# coil.net
KiCad netlist of a schematic drawn in EAGLE
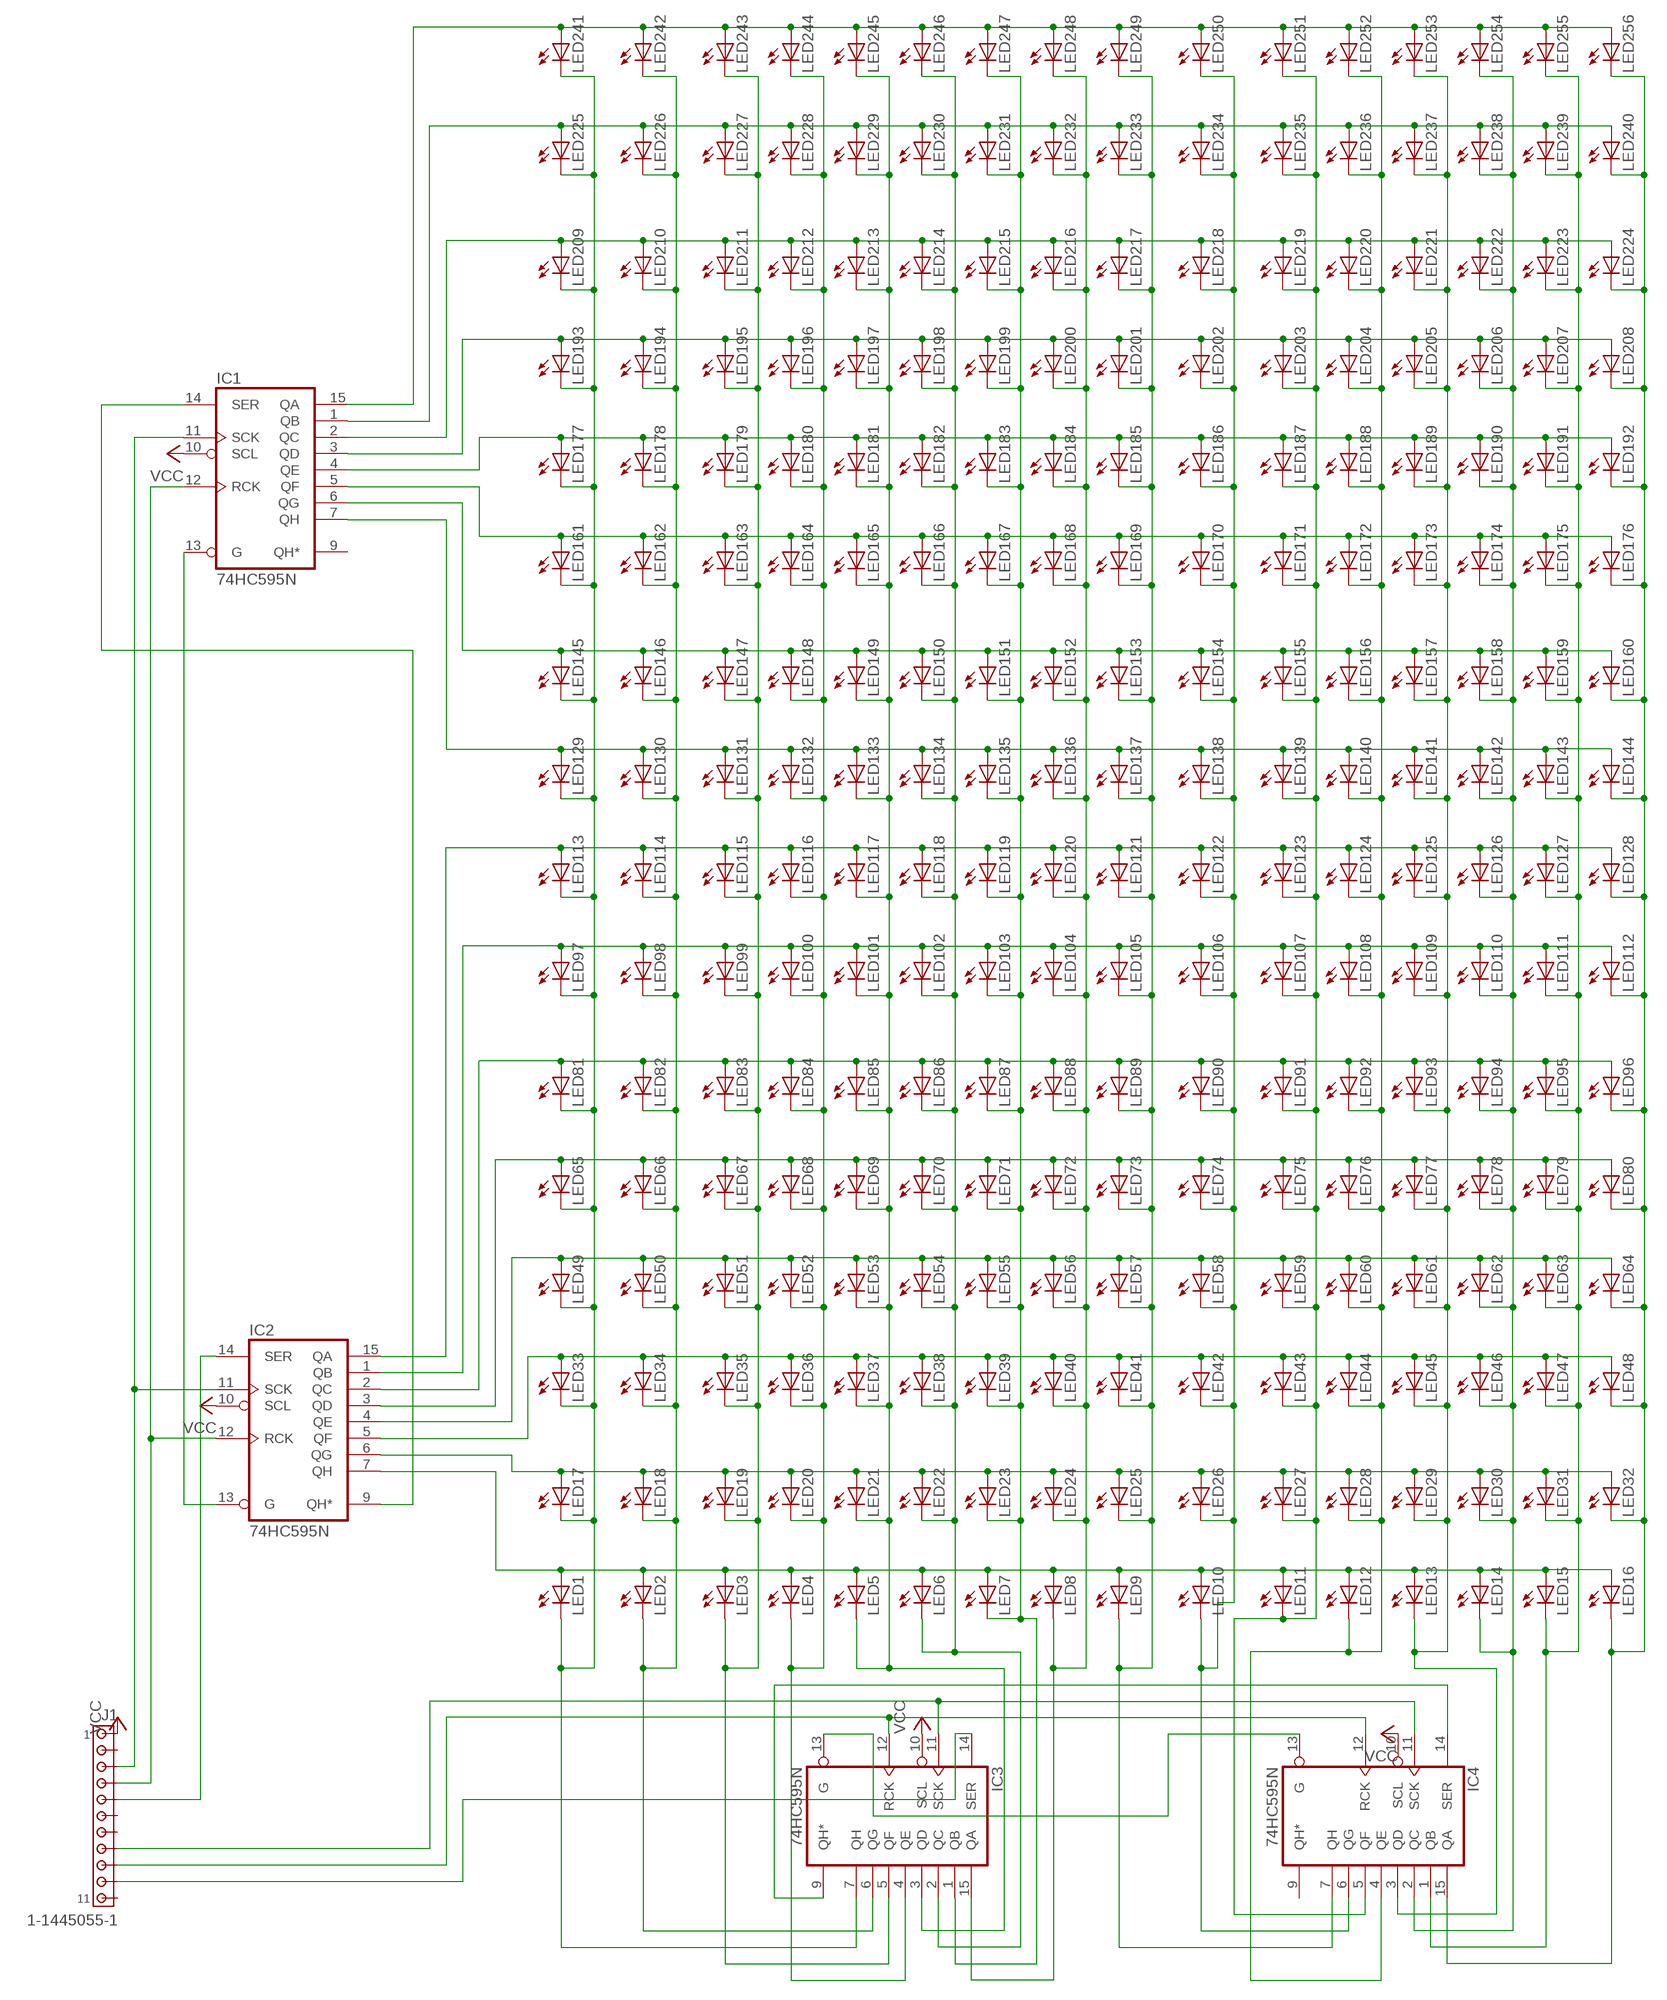
[diagram p0: schematic, sheet 1]

(export (version "E")
  (design (tool "Eeschema 10.0.6"))
  (components
    (comp (ref "IC1")
      (value "74HC595N")
      (footprint "eagle-import:DIL16")
      (libsource (lib "eagle-import") (part "74595NHC"))
    )
    (comp (ref "IC2")
      (value "74HC595N")
      (footprint "eagle-import:DIL16")
      (libsource (lib "eagle-import") (part "74595NHC"))
    )
    (comp (ref "IC3")
      (value "74HC595N")
      (footprint "eagle-import:DIL16")
      (libsource (lib "eagle-import") (part "74595NHC"))
    )
    (comp (ref "IC4")
      (value "74HC595N")
      (footprint "eagle-import:DIL16")
      (libsource (lib "eagle-import") (part "74595NHC"))
    )
    (comp (ref "J1")
      (value "1-1445055-1")
      (footprint "eagle-import:1-1445055-1")
      (libsource (lib "eagle-import") (part "1-1445055-1"))
    )
    (comp (ref "LED1")
      (value "LED5MM")
      (footprint "eagle-import:LED5MM")
      (libsource (lib "eagle-import") (part "LED5MM"))
    )
    (comp (ref "LED2")
      (value "LED5MM")
      (footprint "eagle-import:LED5MM")
      (libsource (lib "eagle-import") (part "LED5MM"))
    )
    (comp (ref "LED3")
      (value "LED5MM")
      (footprint "eagle-import:LED5MM")
      (libsource (lib "eagle-import") (part "LED5MM"))
    )
    (comp (ref "LED4")
      (value "LED5MM")
      (footprint "eagle-import:LED5MM")
      (libsource (lib "eagle-import") (part "LED5MM"))
    )
    (comp (ref "LED5")
      (value "LED5MM")
      (footprint "eagle-import:LED5MM")
      (libsource (lib "eagle-import") (part "LED5MM"))
    )
    (comp (ref "LED6")
      (value "LED5MM")
      (footprint "eagle-import:LED5MM")
      (libsource (lib "eagle-import") (part "LED5MM"))
    )
    (comp (ref "LED7")
      (value "LED5MM")
      (footprint "eagle-import:LED5MM")
      (libsource (lib "eagle-import") (part "LED5MM"))
    )
    (comp (ref "LED8")
      (value "LED5MM")
      (footprint "eagle-import:LED5MM")
      (libsource (lib "eagle-import") (part "LED5MM"))
    )
    (comp (ref "LED9")
      (value "LED5MM")
      (footprint "eagle-import:LED5MM")
      (libsource (lib "eagle-import") (part "LED5MM"))
    )
    (comp (ref "LED10")
      (value "LED5MM")
      (footprint "eagle-import:LED5MM")
      (libsource (lib "eagle-import") (part "LED5MM"))
    )
    (comp (ref "LED11")
      (value "LED5MM")
      (footprint "eagle-import:LED5MM")
      (libsource (lib "eagle-import") (part "LED5MM"))
    )
    (comp (ref "LED12")
      (value "LED5MM")
      (footprint "eagle-import:LED5MM")
      (libsource (lib "eagle-import") (part "LED5MM"))
    )
    (comp (ref "LED13")
      (value "LED5MM")
      (footprint "eagle-import:LED5MM")
      (libsource (lib "eagle-import") (part "LED5MM"))
    )
    (comp (ref "LED14")
      (value "LED5MM")
      (footprint "eagle-import:LED5MM")
      (libsource (lib "eagle-import") (part "LED5MM"))
    )
    (comp (ref "LED15")
      (value "LED5MM")
      (footprint "eagle-import:LED5MM")
      (libsource (lib "eagle-import") (part "LED5MM"))
    )
    (comp (ref "LED16")
      (value "LED5MM")
      (footprint "eagle-import:LED5MM")
      (libsource (lib "eagle-import") (part "LED5MM"))
    )
    (comp (ref "LED17")
      (value "LED5MM")
      (footprint "eagle-import:LED5MM")
      (libsource (lib "eagle-import") (part "LED5MM"))
    )
    (comp (ref "LED18")
      (value "LED5MM")
      (footprint "eagle-import:LED5MM")
      (libsource (lib "eagle-import") (part "LED5MM"))
    )
    (comp (ref "LED19")
      (value "LED5MM")
      (footprint "eagle-import:LED5MM")
      (libsource (lib "eagle-import") (part "LED5MM"))
    )
    (comp (ref "LED20")
      (value "LED5MM")
      (footprint "eagle-import:LED5MM")
      (libsource (lib "eagle-import") (part "LED5MM"))
    )
    (comp (ref "LED21")
      (value "LED5MM")
      (footprint "eagle-import:LED5MM")
      (libsource (lib "eagle-import") (part "LED5MM"))
    )
    (comp (ref "LED22")
      (value "LED5MM")
      (footprint "eagle-import:LED5MM")
      (libsource (lib "eagle-import") (part "LED5MM"))
    )
    (comp (ref "LED23")
      (value "LED5MM")
      (footprint "eagle-import:LED5MM")
      (libsource (lib "eagle-import") (part "LED5MM"))
    )
    (comp (ref "LED24")
      (value "LED5MM")
      (footprint "eagle-import:LED5MM")
      (libsource (lib "eagle-import") (part "LED5MM"))
    )
    (comp (ref "LED25")
      (value "LED5MM")
      (footprint "eagle-import:LED5MM")
      (libsource (lib "eagle-import") (part "LED5MM"))
    )
    (comp (ref "LED26")
      (value "LED5MM")
      (footprint "eagle-import:LED5MM")
      (libsource (lib "eagle-import") (part "LED5MM"))
    )
    (comp (ref "LED27")
      (value "LED5MM")
      (footprint "eagle-import:LED5MM")
      (libsource (lib "eagle-import") (part "LED5MM"))
    )
    (comp (ref "LED28")
      (value "LED5MM")
      (footprint "eagle-import:LED5MM")
      (libsource (lib "eagle-import") (part "LED5MM"))
    )
    (comp (ref "LED29")
      (value "LED5MM")
      (footprint "eagle-import:LED5MM")
      (libsource (lib "eagle-import") (part "LED5MM"))
    )
    (comp (ref "LED30")
      (value "LED5MM")
      (footprint "eagle-import:LED5MM")
      (libsource (lib "eagle-import") (part "LED5MM"))
    )
    (comp (ref "LED31")
      (value "LED5MM")
      (footprint "eagle-import:LED5MM")
      (libsource (lib "eagle-import") (part "LED5MM"))
    )
    (comp (ref "LED32")
      (value "LED5MM")
      (footprint "eagle-import:LED5MM")
      (libsource (lib "eagle-import") (part "LED5MM"))
    )
    (comp (ref "LED33")
      (value "LED5MM")
      (footprint "eagle-import:LED5MM")
      (libsource (lib "eagle-import") (part "LED5MM"))
    )
    (comp (ref "LED34")
      (value "LED5MM")
      (footprint "eagle-import:LED5MM")
      (libsource (lib "eagle-import") (part "LED5MM"))
    )
    (comp (ref "LED35")
      (value "LED5MM")
      (footprint "eagle-import:LED5MM")
      (libsource (lib "eagle-import") (part "LED5MM"))
    )
    (comp (ref "LED36")
      (value "LED5MM")
      (footprint "eagle-import:LED5MM")
      (libsource (lib "eagle-import") (part "LED5MM"))
    )
    (comp (ref "LED37")
      (value "LED5MM")
      (footprint "eagle-import:LED5MM")
      (libsource (lib "eagle-import") (part "LED5MM"))
    )
    (comp (ref "LED38")
      (value "LED5MM")
      (footprint "eagle-import:LED5MM")
      (libsource (lib "eagle-import") (part "LED5MM"))
    )
    (comp (ref "LED39")
      (value "LED5MM")
      (footprint "eagle-import:LED5MM")
      (libsource (lib "eagle-import") (part "LED5MM"))
    )
    (comp (ref "LED40")
      (value "LED5MM")
      (footprint "eagle-import:LED5MM")
      (libsource (lib "eagle-import") (part "LED5MM"))
    )
    (comp (ref "LED41")
      (value "LED5MM")
      (footprint "eagle-import:LED5MM")
      (libsource (lib "eagle-import") (part "LED5MM"))
    )
    (comp (ref "LED42")
      (value "LED5MM")
      (footprint "eagle-import:LED5MM")
      (libsource (lib "eagle-import") (part "LED5MM"))
    )
    (comp (ref "LED43")
      (value "LED5MM")
      (footprint "eagle-import:LED5MM")
      (libsource (lib "eagle-import") (part "LED5MM"))
    )
    (comp (ref "LED44")
      (value "LED5MM")
      (footprint "eagle-import:LED5MM")
      (libsource (lib "eagle-import") (part "LED5MM"))
    )
    (comp (ref "LED45")
      (value "LED5MM")
      (footprint "eagle-import:LED5MM")
      (libsource (lib "eagle-import") (part "LED5MM"))
    )
    (comp (ref "LED46")
      (value "LED5MM")
      (footprint "eagle-import:LED5MM")
      (libsource (lib "eagle-import") (part "LED5MM"))
    )
    (comp (ref "LED47")
      (value "LED5MM")
      (footprint "eagle-import:LED5MM")
      (libsource (lib "eagle-import") (part "LED5MM"))
    )
    (comp (ref "LED48")
      (value "LED5MM")
      (footprint "eagle-import:LED5MM")
      (libsource (lib "eagle-import") (part "LED5MM"))
    )
    (comp (ref "LED49")
      (value "LED5MM")
      (footprint "eagle-import:LED5MM")
      (libsource (lib "eagle-import") (part "LED5MM"))
    )
    (comp (ref "LED50")
      (value "LED5MM")
      (footprint "eagle-import:LED5MM")
      (libsource (lib "eagle-import") (part "LED5MM"))
    )
    (comp (ref "LED51")
      (value "LED5MM")
      (footprint "eagle-import:LED5MM")
      (libsource (lib "eagle-import") (part "LED5MM"))
    )
    (comp (ref "LED52")
      (value "LED5MM")
      (footprint "eagle-import:LED5MM")
      (libsource (lib "eagle-import") (part "LED5MM"))
    )
    (comp (ref "LED53")
      (value "LED5MM")
      (footprint "eagle-import:LED5MM")
      (libsource (lib "eagle-import") (part "LED5MM"))
    )
    (comp (ref "LED54")
      (value "LED5MM")
      (footprint "eagle-import:LED5MM")
      (libsource (lib "eagle-import") (part "LED5MM"))
    )
    (comp (ref "LED55")
      (value "LED5MM")
      (footprint "eagle-import:LED5MM")
      (libsource (lib "eagle-import") (part "LED5MM"))
    )
    (comp (ref "LED56")
      (value "LED5MM")
      (footprint "eagle-import:LED5MM")
      (libsource (lib "eagle-import") (part "LED5MM"))
    )
    (comp (ref "LED57")
      (value "LED5MM")
      (footprint "eagle-import:LED5MM")
      (libsource (lib "eagle-import") (part "LED5MM"))
    )
    (comp (ref "LED58")
      (value "LED5MM")
      (footprint "eagle-import:LED5MM")
      (libsource (lib "eagle-import") (part "LED5MM"))
    )
    (comp (ref "LED59")
      (value "LED5MM")
      (footprint "eagle-import:LED5MM")
      (libsource (lib "eagle-import") (part "LED5MM"))
    )
    (comp (ref "LED60")
      (value "LED5MM")
      (footprint "eagle-import:LED5MM")
      (libsource (lib "eagle-import") (part "LED5MM"))
    )
    (comp (ref "LED61")
      (value "LED5MM")
      (footprint "eagle-import:LED5MM")
      (libsource (lib "eagle-import") (part "LED5MM"))
    )
    (comp (ref "LED62")
      (value "LED5MM")
      (footprint "eagle-import:LED5MM")
      (libsource (lib "eagle-import") (part "LED5MM"))
    )
    (comp (ref "LED63")
      (value "LED5MM")
      (footprint "eagle-import:LED5MM")
      (libsource (lib "eagle-import") (part "LED5MM"))
    )
    (comp (ref "LED64")
      (value "LED5MM")
      (footprint "eagle-import:LED5MM")
      (libsource (lib "eagle-import") (part "LED5MM"))
    )
    (comp (ref "LED65")
      (value "LED5MM")
      (footprint "eagle-import:LED5MM")
      (libsource (lib "eagle-import") (part "LED5MM"))
    )
    (comp (ref "LED66")
      (value "LED5MM")
      (footprint "eagle-import:LED5MM")
      (libsource (lib "eagle-import") (part "LED5MM"))
    )
    (comp (ref "LED67")
      (value "LED5MM")
      (footprint "eagle-import:LED5MM")
      (libsource (lib "eagle-import") (part "LED5MM"))
    )
    (comp (ref "LED68")
      (value "LED5MM")
      (footprint "eagle-import:LED5MM")
      (libsource (lib "eagle-import") (part "LED5MM"))
    )
    (comp (ref "LED69")
      (value "LED5MM")
      (footprint "eagle-import:LED5MM")
      (libsource (lib "eagle-import") (part "LED5MM"))
    )
    (comp (ref "LED70")
      (value "LED5MM")
      (footprint "eagle-import:LED5MM")
      (libsource (lib "eagle-import") (part "LED5MM"))
    )
    (comp (ref "LED71")
      (value "LED5MM")
      (footprint "eagle-import:LED5MM")
      (libsource (lib "eagle-import") (part "LED5MM"))
    )
    (comp (ref "LED72")
      (value "LED5MM")
      (footprint "eagle-import:LED5MM")
      (libsource (lib "eagle-import") (part "LED5MM"))
    )
    (comp (ref "LED73")
      (value "LED5MM")
      (footprint "eagle-import:LED5MM")
      (libsource (lib "eagle-import") (part "LED5MM"))
    )
    (comp (ref "LED74")
      (value "LED5MM")
      (footprint "eagle-import:LED5MM")
      (libsource (lib "eagle-import") (part "LED5MM"))
    )
    (comp (ref "LED75")
      (value "LED5MM")
      (footprint "eagle-import:LED5MM")
      (libsource (lib "eagle-import") (part "LED5MM"))
    )
    (comp (ref "LED76")
      (value "LED5MM")
      (footprint "eagle-import:LED5MM")
      (libsource (lib "eagle-import") (part "LED5MM"))
    )
    (comp (ref "LED77")
      (value "LED5MM")
      (footprint "eagle-import:LED5MM")
      (libsource (lib "eagle-import") (part "LED5MM"))
    )
    (comp (ref "LED78")
      (value "LED5MM")
      (footprint "eagle-import:LED5MM")
      (libsource (lib "eagle-import") (part "LED5MM"))
    )
    (comp (ref "LED79")
      (value "LED5MM")
      (footprint "eagle-import:LED5MM")
      (libsource (lib "eagle-import") (part "LED5MM"))
    )
    (comp (ref "LED80")
      (value "LED5MM")
      (footprint "eagle-import:LED5MM")
      (libsource (lib "eagle-import") (part "LED5MM"))
    )
    (comp (ref "LED81")
      (value "LED5MM")
      (footprint "eagle-import:LED5MM")
      (libsource (lib "eagle-import") (part "LED5MM"))
    )
    (comp (ref "LED82")
      (value "LED5MM")
      (footprint "eagle-import:LED5MM")
      (libsource (lib "eagle-import") (part "LED5MM"))
    )
    (comp (ref "LED83")
      (value "LED5MM")
      (footprint "eagle-import:LED5MM")
      (libsource (lib "eagle-import") (part "LED5MM"))
    )
    (comp (ref "LED84")
      (value "LED5MM")
      (footprint "eagle-import:LED5MM")
      (libsource (lib "eagle-import") (part "LED5MM"))
    )
    (comp (ref "LED85")
      (value "LED5MM")
      (footprint "eagle-import:LED5MM")
      (libsource (lib "eagle-import") (part "LED5MM"))
    )
    (comp (ref "LED86")
      (value "LED5MM")
      (footprint "eagle-import:LED5MM")
      (libsource (lib "eagle-import") (part "LED5MM"))
    )
    (comp (ref "LED87")
      (value "LED5MM")
      (footprint "eagle-import:LED5MM")
      (libsource (lib "eagle-import") (part "LED5MM"))
    )
    (comp (ref "LED88")
      (value "LED5MM")
      (footprint "eagle-import:LED5MM")
      (libsource (lib "eagle-import") (part "LED5MM"))
    )
    (comp (ref "LED89")
      (value "LED5MM")
      (footprint "eagle-import:LED5MM")
      (libsource (lib "eagle-import") (part "LED5MM"))
    )
    (comp (ref "LED90")
      (value "LED5MM")
      (footprint "eagle-import:LED5MM")
      (libsource (lib "eagle-import") (part "LED5MM"))
    )
    (comp (ref "LED91")
      (value "LED5MM")
      (footprint "eagle-import:LED5MM")
      (libsource (lib "eagle-import") (part "LED5MM"))
    )
    (comp (ref "LED92")
      (value "LED5MM")
      (footprint "eagle-import:LED5MM")
      (libsource (lib "eagle-import") (part "LED5MM"))
    )
    (comp (ref "LED93")
      (value "LED5MM")
      (footprint "eagle-import:LED5MM")
      (libsource (lib "eagle-import") (part "LED5MM"))
    )
    (comp (ref "LED94")
      (value "LED5MM")
      (footprint "eagle-import:LED5MM")
      (libsource (lib "eagle-import") (part "LED5MM"))
    )
    (comp (ref "LED95")
      (value "LED5MM")
      (footprint "eagle-import:LED5MM")
      (libsource (lib "eagle-import") (part "LED5MM"))
    )
    (comp (ref "LED96")
      (value "LED5MM")
      (footprint "eagle-import:LED5MM")
      (libsource (lib "eagle-import") (part "LED5MM"))
    )
    (comp (ref "LED97")
      (value "LED5MM")
      (footprint "eagle-import:LED5MM")
      (libsource (lib "eagle-import") (part "LED5MM"))
    )
    (comp (ref "LED98")
      (value "LED5MM")
      (footprint "eagle-import:LED5MM")
      (libsource (lib "eagle-import") (part "LED5MM"))
    )
    (comp (ref "LED99")
      (value "LED5MM")
      (footprint "eagle-import:LED5MM")
      (libsource (lib "eagle-import") (part "LED5MM"))
    )
    (comp (ref "LED100")
      (value "LED5MM")
      (footprint "eagle-import:LED5MM")
      (libsource (lib "eagle-import") (part "LED5MM"))
    )
    (comp (ref "LED101")
      (value "LED5MM")
      (footprint "eagle-import:LED5MM")
      (libsource (lib "eagle-import") (part "LED5MM"))
    )
    (comp (ref "LED102")
      (value "LED5MM")
      (footprint "eagle-import:LED5MM")
      (libsource (lib "eagle-import") (part "LED5MM"))
    )
    (comp (ref "LED103")
      (value "LED5MM")
      (footprint "eagle-import:LED5MM")
      (libsource (lib "eagle-import") (part "LED5MM"))
    )
    (comp (ref "LED104")
      (value "LED5MM")
      (footprint "eagle-import:LED5MM")
      (libsource (lib "eagle-import") (part "LED5MM"))
    )
    (comp (ref "LED105")
      (value "LED5MM")
      (footprint "eagle-import:LED5MM")
      (libsource (lib "eagle-import") (part "LED5MM"))
    )
    (comp (ref "LED106")
      (value "LED5MM")
      (footprint "eagle-import:LED5MM")
      (libsource (lib "eagle-import") (part "LED5MM"))
    )
    (comp (ref "LED107")
      (value "LED5MM")
      (footprint "eagle-import:LED5MM")
      (libsource (lib "eagle-import") (part "LED5MM"))
    )
    (comp (ref "LED108")
      (value "LED5MM")
      (footprint "eagle-import:LED5MM")
      (libsource (lib "eagle-import") (part "LED5MM"))
    )
    (comp (ref "LED109")
      (value "LED5MM")
      (footprint "eagle-import:LED5MM")
      (libsource (lib "eagle-import") (part "LED5MM"))
    )
    (comp (ref "LED110")
      (value "LED5MM")
      (footprint "eagle-import:LED5MM")
      (libsource (lib "eagle-import") (part "LED5MM"))
    )
    (comp (ref "LED111")
      (value "LED5MM")
      (footprint "eagle-import:LED5MM")
      (libsource (lib "eagle-import") (part "LED5MM"))
    )
    (comp (ref "LED112")
      (value "LED5MM")
      (footprint "eagle-import:LED5MM")
      (libsource (lib "eagle-import") (part "LED5MM"))
    )
    (comp (ref "LED113")
      (value "LED5MM")
      (footprint "eagle-import:LED5MM")
      (libsource (lib "eagle-import") (part "LED5MM"))
    )
    (comp (ref "LED114")
      (value "LED5MM")
      (footprint "eagle-import:LED5MM")
      (libsource (lib "eagle-import") (part "LED5MM"))
    )
    (comp (ref "LED115")
      (value "LED5MM")
      (footprint "eagle-import:LED5MM")
      (libsource (lib "eagle-import") (part "LED5MM"))
    )
    (comp (ref "LED116")
      (value "LED5MM")
      (footprint "eagle-import:LED5MM")
      (libsource (lib "eagle-import") (part "LED5MM"))
    )
    (comp (ref "LED117")
      (value "LED5MM")
      (footprint "eagle-import:LED5MM")
      (libsource (lib "eagle-import") (part "LED5MM"))
    )
    (comp (ref "LED118")
      (value "LED5MM")
      (footprint "eagle-import:LED5MM")
      (libsource (lib "eagle-import") (part "LED5MM"))
    )
    (comp (ref "LED119")
      (value "LED5MM")
      (footprint "eagle-import:LED5MM")
      (libsource (lib "eagle-import") (part "LED5MM"))
    )
    (comp (ref "LED120")
      (value "LED5MM")
      (footprint "eagle-import:LED5MM")
      (libsource (lib "eagle-import") (part "LED5MM"))
    )
    (comp (ref "LED121")
      (value "LED5MM")
      (footprint "eagle-import:LED5MM")
      (libsource (lib "eagle-import") (part "LED5MM"))
    )
    (comp (ref "LED122")
      (value "LED5MM")
      (footprint "eagle-import:LED5MM")
      (libsource (lib "eagle-import") (part "LED5MM"))
    )
    (comp (ref "LED123")
      (value "LED5MM")
      (footprint "eagle-import:LED5MM")
      (libsource (lib "eagle-import") (part "LED5MM"))
    )
    (comp (ref "LED124")
      (value "LED5MM")
      (footprint "eagle-import:LED5MM")
      (libsource (lib "eagle-import") (part "LED5MM"))
    )
    (comp (ref "LED125")
      (value "LED5MM")
      (footprint "eagle-import:LED5MM")
      (libsource (lib "eagle-import") (part "LED5MM"))
    )
    (comp (ref "LED126")
      (value "LED5MM")
      (footprint "eagle-import:LED5MM")
      (libsource (lib "eagle-import") (part "LED5MM"))
    )
    (comp (ref "LED127")
      (value "LED5MM")
      (footprint "eagle-import:LED5MM")
      (libsource (lib "eagle-import") (part "LED5MM"))
    )
    (comp (ref "LED128")
      (value "LED5MM")
      (footprint "eagle-import:LED5MM")
      (libsource (lib "eagle-import") (part "LED5MM"))
    )
    (comp (ref "LED129")
      (value "LED5MM")
      (footprint "eagle-import:LED5MM")
      (libsource (lib "eagle-import") (part "LED5MM"))
    )
    (comp (ref "LED130")
      (value "LED5MM")
      (footprint "eagle-import:LED5MM")
      (libsource (lib "eagle-import") (part "LED5MM"))
    )
    (comp (ref "LED131")
      (value "LED5MM")
      (footprint "eagle-import:LED5MM")
      (libsource (lib "eagle-import") (part "LED5MM"))
    )
    (comp (ref "LED132")
      (value "LED5MM")
      (footprint "eagle-import:LED5MM")
      (libsource (lib "eagle-import") (part "LED5MM"))
    )
    (comp (ref "LED133")
      (value "LED5MM")
      (footprint "eagle-import:LED5MM")
      (libsource (lib "eagle-import") (part "LED5MM"))
    )
    (comp (ref "LED134")
      (value "LED5MM")
      (footprint "eagle-import:LED5MM")
      (libsource (lib "eagle-import") (part "LED5MM"))
    )
    (comp (ref "LED135")
      (value "LED5MM")
      (footprint "eagle-import:LED5MM")
      (libsource (lib "eagle-import") (part "LED5MM"))
    )
    (comp (ref "LED136")
      (value "LED5MM")
      (footprint "eagle-import:LED5MM")
      (libsource (lib "eagle-import") (part "LED5MM"))
    )
    (comp (ref "LED137")
      (value "LED5MM")
      (footprint "eagle-import:LED5MM")
      (libsource (lib "eagle-import") (part "LED5MM"))
    )
    (comp (ref "LED138")
      (value "LED5MM")
      (footprint "eagle-import:LED5MM")
      (libsource (lib "eagle-import") (part "LED5MM"))
    )
    (comp (ref "LED139")
      (value "LED5MM")
      (footprint "eagle-import:LED5MM")
      (libsource (lib "eagle-import") (part "LED5MM"))
    )
    (comp (ref "LED140")
      (value "LED5MM")
      (footprint "eagle-import:LED5MM")
      (libsource (lib "eagle-import") (part "LED5MM"))
    )
    (comp (ref "LED141")
      (value "LED5MM")
      (footprint "eagle-import:LED5MM")
      (libsource (lib "eagle-import") (part "LED5MM"))
    )
    (comp (ref "LED142")
      (value "LED5MM")
      (footprint "eagle-import:LED5MM")
      (libsource (lib "eagle-import") (part "LED5MM"))
    )
    (comp (ref "LED143")
      (value "LED5MM")
      (footprint "eagle-import:LED5MM")
      (libsource (lib "eagle-import") (part "LED5MM"))
    )
    (comp (ref "LED144")
      (value "LED5MM")
      (footprint "eagle-import:LED5MM")
      (libsource (lib "eagle-import") (part "LED5MM"))
    )
    (comp (ref "LED145")
      (value "LED5MM")
      (footprint "eagle-import:LED5MM")
      (libsource (lib "eagle-import") (part "LED5MM"))
    )
    (comp (ref "LED146")
      (value "LED5MM")
      (footprint "eagle-import:LED5MM")
      (libsource (lib "eagle-import") (part "LED5MM"))
    )
    (comp (ref "LED147")
      (value "LED5MM")
      (footprint "eagle-import:LED5MM")
      (libsource (lib "eagle-import") (part "LED5MM"))
    )
    (comp (ref "LED148")
      (value "LED5MM")
      (footprint "eagle-import:LED5MM")
      (libsource (lib "eagle-import") (part "LED5MM"))
    )
    (comp (ref "LED149")
      (value "LED5MM")
      (footprint "eagle-import:LED5MM")
      (libsource (lib "eagle-import") (part "LED5MM"))
    )
    (comp (ref "LED150")
      (value "LED5MM")
      (footprint "eagle-import:LED5MM")
      (libsource (lib "eagle-import") (part "LED5MM"))
    )
    (comp (ref "LED151")
      (value "LED5MM")
      (footprint "eagle-import:LED5MM")
      (libsource (lib "eagle-import") (part "LED5MM"))
    )
    (comp (ref "LED152")
      (value "LED5MM")
      (footprint "eagle-import:LED5MM")
      (libsource (lib "eagle-import") (part "LED5MM"))
    )
    (comp (ref "LED153")
      (value "LED5MM")
      (footprint "eagle-import:LED5MM")
      (libsource (lib "eagle-import") (part "LED5MM"))
    )
    (comp (ref "LED154")
      (value "LED5MM")
      (footprint "eagle-import:LED5MM")
      (libsource (lib "eagle-import") (part "LED5MM"))
    )
    (comp (ref "LED155")
      (value "LED5MM")
      (footprint "eagle-import:LED5MM")
      (libsource (lib "eagle-import") (part "LED5MM"))
    )
    (comp (ref "LED156")
      (value "LED5MM")
      (footprint "eagle-import:LED5MM")
      (libsource (lib "eagle-import") (part "LED5MM"))
    )
    (comp (ref "LED157")
      (value "LED5MM")
      (footprint "eagle-import:LED5MM")
      (libsource (lib "eagle-import") (part "LED5MM"))
    )
    (comp (ref "LED158")
      (value "LED5MM")
      (footprint "eagle-import:LED5MM")
      (libsource (lib "eagle-import") (part "LED5MM"))
    )
    (comp (ref "LED159")
      (value "LED5MM")
      (footprint "eagle-import:LED5MM")
      (libsource (lib "eagle-import") (part "LED5MM"))
    )
    (comp (ref "LED160")
      (value "LED5MM")
      (footprint "eagle-import:LED5MM")
      (libsource (lib "eagle-import") (part "LED5MM"))
    )
    (comp (ref "LED161")
      (value "LED5MM")
      (footprint "eagle-import:LED5MM")
      (libsource (lib "eagle-import") (part "LED5MM"))
    )
    (comp (ref "LED162")
      (value "LED5MM")
      (footprint "eagle-import:LED5MM")
      (libsource (lib "eagle-import") (part "LED5MM"))
    )
    (comp (ref "LED163")
      (value "LED5MM")
      (footprint "eagle-import:LED5MM")
      (libsource (lib "eagle-import") (part "LED5MM"))
    )
    (comp (ref "LED164")
      (value "LED5MM")
      (footprint "eagle-import:LED5MM")
      (libsource (lib "eagle-import") (part "LED5MM"))
    )
    (comp (ref "LED165")
      (value "LED5MM")
      (footprint "eagle-import:LED5MM")
      (libsource (lib "eagle-import") (part "LED5MM"))
    )
    (comp (ref "LED166")
      (value "LED5MM")
      (footprint "eagle-import:LED5MM")
      (libsource (lib "eagle-import") (part "LED5MM"))
    )
    (comp (ref "LED167")
      (value "LED5MM")
      (footprint "eagle-import:LED5MM")
      (libsource (lib "eagle-import") (part "LED5MM"))
    )
    (comp (ref "LED168")
      (value "LED5MM")
      (footprint "eagle-import:LED5MM")
      (libsource (lib "eagle-import") (part "LED5MM"))
    )
    (comp (ref "LED169")
      (value "LED5MM")
      (footprint "eagle-import:LED5MM")
      (libsource (lib "eagle-import") (part "LED5MM"))
    )
    (comp (ref "LED170")
      (value "LED5MM")
      (footprint "eagle-import:LED5MM")
      (libsource (lib "eagle-import") (part "LED5MM"))
    )
    (comp (ref "LED171")
      (value "LED5MM")
      (footprint "eagle-import:LED5MM")
      (libsource (lib "eagle-import") (part "LED5MM"))
    )
    (comp (ref "LED172")
      (value "LED5MM")
      (footprint "eagle-import:LED5MM")
      (libsource (lib "eagle-import") (part "LED5MM"))
    )
    (comp (ref "LED173")
      (value "LED5MM")
      (footprint "eagle-import:LED5MM")
      (libsource (lib "eagle-import") (part "LED5MM"))
    )
    (comp (ref "LED174")
      (value "LED5MM")
      (footprint "eagle-import:LED5MM")
      (libsource (lib "eagle-import") (part "LED5MM"))
    )
    (comp (ref "LED175")
      (value "LED5MM")
      (footprint "eagle-import:LED5MM")
      (libsource (lib "eagle-import") (part "LED5MM"))
    )
    (comp (ref "LED176")
      (value "LED5MM")
      (footprint "eagle-import:LED5MM")
      (libsource (lib "eagle-import") (part "LED5MM"))
    )
    (comp (ref "LED177")
      (value "LED5MM")
      (footprint "eagle-import:LED5MM")
      (libsource (lib "eagle-import") (part "LED5MM"))
    )
    (comp (ref "LED178")
      (value "LED5MM")
      (footprint "eagle-import:LED5MM")
      (libsource (lib "eagle-import") (part "LED5MM"))
    )
    (comp (ref "LED179")
      (value "LED5MM")
      (footprint "eagle-import:LED5MM")
      (libsource (lib "eagle-import") (part "LED5MM"))
    )
    (comp (ref "LED180")
      (value "LED5MM")
      (footprint "eagle-import:LED5MM")
      (libsource (lib "eagle-import") (part "LED5MM"))
    )
    (comp (ref "LED181")
      (value "LED5MM")
      (footprint "eagle-import:LED5MM")
      (libsource (lib "eagle-import") (part "LED5MM"))
    )
    (comp (ref "LED182")
      (value "LED5MM")
      (footprint "eagle-import:LED5MM")
      (libsource (lib "eagle-import") (part "LED5MM"))
    )
    (comp (ref "LED183")
      (value "LED5MM")
      (footprint "eagle-import:LED5MM")
      (libsource (lib "eagle-import") (part "LED5MM"))
    )
    (comp (ref "LED184")
      (value "LED5MM")
      (footprint "eagle-import:LED5MM")
      (libsource (lib "eagle-import") (part "LED5MM"))
    )
    (comp (ref "LED185")
      (value "LED5MM")
      (footprint "eagle-import:LED5MM")
      (libsource (lib "eagle-import") (part "LED5MM"))
    )
    (comp (ref "LED186")
      (value "LED5MM")
      (footprint "eagle-import:LED5MM")
      (libsource (lib "eagle-import") (part "LED5MM"))
    )
    (comp (ref "LED187")
      (value "LED5MM")
      (footprint "eagle-import:LED5MM")
      (libsource (lib "eagle-import") (part "LED5MM"))
    )
    (comp (ref "LED188")
      (value "LED5MM")
      (footprint "eagle-import:LED5MM")
      (libsource (lib "eagle-import") (part "LED5MM"))
    )
    (comp (ref "LED189")
      (value "LED5MM")
      (footprint "eagle-import:LED5MM")
      (libsource (lib "eagle-import") (part "LED5MM"))
    )
    (comp (ref "LED190")
      (value "LED5MM")
      (footprint "eagle-import:LED5MM")
      (libsource (lib "eagle-import") (part "LED5MM"))
    )
    (comp (ref "LED191")
      (value "LED5MM")
      (footprint "eagle-import:LED5MM")
      (libsource (lib "eagle-import") (part "LED5MM"))
    )
    (comp (ref "LED192")
      (value "LED5MM")
      (footprint "eagle-import:LED5MM")
      (libsource (lib "eagle-import") (part "LED5MM"))
    )
    (comp (ref "LED193")
      (value "LED5MM")
      (footprint "eagle-import:LED5MM")
      (libsource (lib "eagle-import") (part "LED5MM"))
    )
    (comp (ref "LED194")
      (value "LED5MM")
      (footprint "eagle-import:LED5MM")
      (libsource (lib "eagle-import") (part "LED5MM"))
    )
    (comp (ref "LED195")
      (value "LED5MM")
      (footprint "eagle-import:LED5MM")
      (libsource (lib "eagle-import") (part "LED5MM"))
    )
    (comp (ref "LED196")
      (value "LED5MM")
      (footprint "eagle-import:LED5MM")
      (libsource (lib "eagle-import") (part "LED5MM"))
    )
    (comp (ref "LED197")
      (value "LED5MM")
      (footprint "eagle-import:LED5MM")
      (libsource (lib "eagle-import") (part "LED5MM"))
    )
    (comp (ref "LED198")
      (value "LED5MM")
      (footprint "eagle-import:LED5MM")
      (libsource (lib "eagle-import") (part "LED5MM"))
    )
    (comp (ref "LED199")
      (value "LED5MM")
      (footprint "eagle-import:LED5MM")
      (libsource (lib "eagle-import") (part "LED5MM"))
    )
    (comp (ref "LED200")
      (value "LED5MM")
      (footprint "eagle-import:LED5MM")
      (libsource (lib "eagle-import") (part "LED5MM"))
    )
    (comp (ref "LED201")
      (value "LED5MM")
      (footprint "eagle-import:LED5MM")
      (libsource (lib "eagle-import") (part "LED5MM"))
    )
    (comp (ref "LED202")
      (value "LED5MM")
      (footprint "eagle-import:LED5MM")
      (libsource (lib "eagle-import") (part "LED5MM"))
    )
    (comp (ref "LED203")
      (value "LED5MM")
      (footprint "eagle-import:LED5MM")
      (libsource (lib "eagle-import") (part "LED5MM"))
    )
    (comp (ref "LED204")
      (value "LED5MM")
      (footprint "eagle-import:LED5MM")
      (libsource (lib "eagle-import") (part "LED5MM"))
    )
    (comp (ref "LED205")
      (value "LED5MM")
      (footprint "eagle-import:LED5MM")
      (libsource (lib "eagle-import") (part "LED5MM"))
    )
    (comp (ref "LED206")
      (value "LED5MM")
      (footprint "eagle-import:LED5MM")
      (libsource (lib "eagle-import") (part "LED5MM"))
    )
    (comp (ref "LED207")
      (value "LED5MM")
      (footprint "eagle-import:LED5MM")
      (libsource (lib "eagle-import") (part "LED5MM"))
    )
    (comp (ref "LED208")
      (value "LED5MM")
      (footprint "eagle-import:LED5MM")
      (libsource (lib "eagle-import") (part "LED5MM"))
    )
    (comp (ref "LED209")
      (value "LED5MM")
      (footprint "eagle-import:LED5MM")
      (libsource (lib "eagle-import") (part "LED5MM"))
    )
    (comp (ref "LED210")
      (value "LED5MM")
      (footprint "eagle-import:LED5MM")
      (libsource (lib "eagle-import") (part "LED5MM"))
    )
    (comp (ref "LED211")
      (value "LED5MM")
      (footprint "eagle-import:LED5MM")
      (libsource (lib "eagle-import") (part "LED5MM"))
    )
    (comp (ref "LED212")
      (value "LED5MM")
      (footprint "eagle-import:LED5MM")
      (libsource (lib "eagle-import") (part "LED5MM"))
    )
    (comp (ref "LED213")
      (value "LED5MM")
      (footprint "eagle-import:LED5MM")
      (libsource (lib "eagle-import") (part "LED5MM"))
    )
    (comp (ref "LED214")
      (value "LED5MM")
      (footprint "eagle-import:LED5MM")
      (libsource (lib "eagle-import") (part "LED5MM"))
    )
    (comp (ref "LED215")
      (value "LED5MM")
      (footprint "eagle-import:LED5MM")
      (libsource (lib "eagle-import") (part "LED5MM"))
    )
    (comp (ref "LED216")
      (value "LED5MM")
      (footprint "eagle-import:LED5MM")
      (libsource (lib "eagle-import") (part "LED5MM"))
    )
    (comp (ref "LED217")
      (value "LED5MM")
      (footprint "eagle-import:LED5MM")
      (libsource (lib "eagle-import") (part "LED5MM"))
    )
    (comp (ref "LED218")
      (value "LED5MM")
      (footprint "eagle-import:LED5MM")
      (libsource (lib "eagle-import") (part "LED5MM"))
    )
    (comp (ref "LED219")
      (value "LED5MM")
      (footprint "eagle-import:LED5MM")
      (libsource (lib "eagle-import") (part "LED5MM"))
    )
    (comp (ref "LED220")
      (value "LED5MM")
      (footprint "eagle-import:LED5MM")
      (libsource (lib "eagle-import") (part "LED5MM"))
    )
    (comp (ref "LED221")
      (value "LED5MM")
      (footprint "eagle-import:LED5MM")
      (libsource (lib "eagle-import") (part "LED5MM"))
    )
    (comp (ref "LED222")
      (value "LED5MM")
      (footprint "eagle-import:LED5MM")
      (libsource (lib "eagle-import") (part "LED5MM"))
    )
    (comp (ref "LED223")
      (value "LED5MM")
      (footprint "eagle-import:LED5MM")
      (libsource (lib "eagle-import") (part "LED5MM"))
    )
    (comp (ref "LED224")
      (value "LED5MM")
      (footprint "eagle-import:LED5MM")
      (libsource (lib "eagle-import") (part "LED5MM"))
    )
    (comp (ref "LED225")
      (value "LED5MM")
      (footprint "eagle-import:LED5MM")
      (libsource (lib "eagle-import") (part "LED5MM"))
    )
    (comp (ref "LED226")
      (value "LED5MM")
      (footprint "eagle-import:LED5MM")
      (libsource (lib "eagle-import") (part "LED5MM"))
    )
    (comp (ref "LED227")
      (value "LED5MM")
      (footprint "eagle-import:LED5MM")
      (libsource (lib "eagle-import") (part "LED5MM"))
    )
    (comp (ref "LED228")
      (value "LED5MM")
      (footprint "eagle-import:LED5MM")
      (libsource (lib "eagle-import") (part "LED5MM"))
    )
    (comp (ref "LED229")
      (value "LED5MM")
      (footprint "eagle-import:LED5MM")
      (libsource (lib "eagle-import") (part "LED5MM"))
    )
    (comp (ref "LED230")
      (value "LED5MM")
      (footprint "eagle-import:LED5MM")
      (libsource (lib "eagle-import") (part "LED5MM"))
    )
    (comp (ref "LED231")
      (value "LED5MM")
      (footprint "eagle-import:LED5MM")
      (libsource (lib "eagle-import") (part "LED5MM"))
    )
    (comp (ref "LED232")
      (value "LED5MM")
      (footprint "eagle-import:LED5MM")
      (libsource (lib "eagle-import") (part "LED5MM"))
    )
    (comp (ref "LED233")
      (value "LED5MM")
      (footprint "eagle-import:LED5MM")
      (libsource (lib "eagle-import") (part "LED5MM"))
    )
    (comp (ref "LED234")
      (value "LED5MM")
      (footprint "eagle-import:LED5MM")
      (libsource (lib "eagle-import") (part "LED5MM"))
    )
    (comp (ref "LED235")
      (value "LED5MM")
      (footprint "eagle-import:LED5MM")
      (libsource (lib "eagle-import") (part "LED5MM"))
    )
    (comp (ref "LED236")
      (value "LED5MM")
      (footprint "eagle-import:LED5MM")
      (libsource (lib "eagle-import") (part "LED5MM"))
    )
    (comp (ref "LED237")
      (value "LED5MM")
      (footprint "eagle-import:LED5MM")
      (libsource (lib "eagle-import") (part "LED5MM"))
    )
    (comp (ref "LED238")
      (value "LED5MM")
      (footprint "eagle-import:LED5MM")
      (libsource (lib "eagle-import") (part "LED5MM"))
    )
    (comp (ref "LED239")
      (value "LED5MM")
      (footprint "eagle-import:LED5MM")
      (libsource (lib "eagle-import") (part "LED5MM"))
    )
    (comp (ref "LED240")
      (value "LED5MM")
      (footprint "eagle-import:LED5MM")
      (libsource (lib "eagle-import") (part "LED5MM"))
    )
    (comp (ref "LED241")
      (value "LED5MM")
      (footprint "eagle-import:LED5MM")
      (libsource (lib "eagle-import") (part "LED5MM"))
    )
    (comp (ref "LED242")
      (value "LED5MM")
      (footprint "eagle-import:LED5MM")
      (libsource (lib "eagle-import") (part "LED5MM"))
    )
    (comp (ref "LED243")
      (value "LED5MM")
      (footprint "eagle-import:LED5MM")
      (libsource (lib "eagle-import") (part "LED5MM"))
    )
    (comp (ref "LED244")
      (value "LED5MM")
      (footprint "eagle-import:LED5MM")
      (libsource (lib "eagle-import") (part "LED5MM"))
    )
    (comp (ref "LED245")
      (value "LED5MM")
      (footprint "eagle-import:LED5MM")
      (libsource (lib "eagle-import") (part "LED5MM"))
    )
    (comp (ref "LED246")
      (value "LED5MM")
      (footprint "eagle-import:LED5MM")
      (libsource (lib "eagle-import") (part "LED5MM"))
    )
    (comp (ref "LED247")
      (value "LED5MM")
      (footprint "eagle-import:LED5MM")
      (libsource (lib "eagle-import") (part "LED5MM"))
    )
    (comp (ref "LED248")
      (value "LED5MM")
      (footprint "eagle-import:LED5MM")
      (libsource (lib "eagle-import") (part "LED5MM"))
    )
    (comp (ref "LED249")
      (value "LED5MM")
      (footprint "eagle-import:LED5MM")
      (libsource (lib "eagle-import") (part "LED5MM"))
    )
    (comp (ref "LED250")
      (value "LED5MM")
      (footprint "eagle-import:LED5MM")
      (libsource (lib "eagle-import") (part "LED5MM"))
    )
    (comp (ref "LED251")
      (value "LED5MM")
      (footprint "eagle-import:LED5MM")
      (libsource (lib "eagle-import") (part "LED5MM"))
    )
    (comp (ref "LED252")
      (value "LED5MM")
      (footprint "eagle-import:LED5MM")
      (libsource (lib "eagle-import") (part "LED5MM"))
    )
    (comp (ref "LED253")
      (value "LED5MM")
      (footprint "eagle-import:LED5MM")
      (libsource (lib "eagle-import") (part "LED5MM"))
    )
    (comp (ref "LED254")
      (value "LED5MM")
      (footprint "eagle-import:LED5MM")
      (libsource (lib "eagle-import") (part "LED5MM"))
    )
    (comp (ref "LED255")
      (value "LED5MM")
      (footprint "eagle-import:LED5MM")
      (libsource (lib "eagle-import") (part "LED5MM"))
    )
    (comp (ref "LED256")
      (value "LED5MM")
      (footprint "eagle-import:LED5MM")
      (libsource (lib "eagle-import") (part "LED5MM"))
    )
  )
  (nets
    (net (code "1") (name "Net-(IC1A-G)") (class "Default")
      (node (ref "IC1") (pin "13") (pinfunction "G_13") (pintype "input"))
      (node (ref "IC2") (pin "13") (pinfunction "G_13") (pintype "input"))
    )
    (net (code "2") (name "Net-(IC1A-QA)") (class "Default")
      (node (ref "IC1") (pin "15") (pinfunction "QA_15") (pintype "tri_state"))
      (node (ref "LED241") (pin "A") (pinfunction "A_A") (pintype "passive"))
      (node (ref "LED242") (pin "A") (pinfunction "A_A") (pintype "passive"))
      (node (ref "LED243") (pin "A") (pinfunction "A_A") (pintype "passive"))
      (node (ref "LED244") (pin "A") (pinfunction "A_A") (pintype "passive"))
      (node (ref "LED245") (pin "A") (pinfunction "A_A") (pintype "passive"))
      (node (ref "LED246") (pin "A") (pinfunction "A_A") (pintype "passive"))
      (node (ref "LED247") (pin "A") (pinfunction "A_A") (pintype "passive"))
      (node (ref "LED248") (pin "A") (pinfunction "A_A") (pintype "passive"))
      (node (ref "LED249") (pin "A") (pinfunction "A_A") (pintype "passive"))
      (node (ref "LED250") (pin "A") (pinfunction "A_A") (pintype "passive"))
      (node (ref "LED251") (pin "A") (pinfunction "A_A") (pintype "passive"))
      (node (ref "LED252") (pin "A") (pinfunction "A_A") (pintype "passive"))
      (node (ref "LED253") (pin "A") (pinfunction "A_A") (pintype "passive"))
      (node (ref "LED254") (pin "A") (pinfunction "A_A") (pintype "passive"))
      (node (ref "LED255") (pin "A") (pinfunction "A_A") (pintype "passive"))
      (node (ref "LED256") (pin "A") (pinfunction "A_A") (pintype "passive"))
    )
    (net (code "3") (name "Net-(IC1A-QB)") (class "Default")
      (node (ref "IC1") (pin "1") (pinfunction "QB_1") (pintype "tri_state"))
      (node (ref "LED225") (pin "A") (pinfunction "A_A") (pintype "passive"))
      (node (ref "LED226") (pin "A") (pinfunction "A_A") (pintype "passive"))
      (node (ref "LED227") (pin "A") (pinfunction "A_A") (pintype "passive"))
      (node (ref "LED228") (pin "A") (pinfunction "A_A") (pintype "passive"))
      (node (ref "LED229") (pin "A") (pinfunction "A_A") (pintype "passive"))
      (node (ref "LED230") (pin "A") (pinfunction "A_A") (pintype "passive"))
      (node (ref "LED231") (pin "A") (pinfunction "A_A") (pintype "passive"))
      (node (ref "LED232") (pin "A") (pinfunction "A_A") (pintype "passive"))
      (node (ref "LED233") (pin "A") (pinfunction "A_A") (pintype "passive"))
      (node (ref "LED234") (pin "A") (pinfunction "A_A") (pintype "passive"))
      (node (ref "LED235") (pin "A") (pinfunction "A_A") (pintype "passive"))
      (node (ref "LED236") (pin "A") (pinfunction "A_A") (pintype "passive"))
      (node (ref "LED237") (pin "A") (pinfunction "A_A") (pintype "passive"))
      (node (ref "LED238") (pin "A") (pinfunction "A_A") (pintype "passive"))
      (node (ref "LED239") (pin "A") (pinfunction "A_A") (pintype "passive"))
      (node (ref "LED240") (pin "A") (pinfunction "A_A") (pintype "passive"))
    )
    (net (code "4") (name "Net-(IC1A-QC)") (class "Default")
      (node (ref "IC1") (pin "2") (pinfunction "QC_2") (pintype "tri_state"))
      (node (ref "LED209") (pin "A") (pinfunction "A_A") (pintype "passive"))
      (node (ref "LED210") (pin "A") (pinfunction "A_A") (pintype "passive"))
      (node (ref "LED211") (pin "A") (pinfunction "A_A") (pintype "passive"))
      (node (ref "LED212") (pin "A") (pinfunction "A_A") (pintype "passive"))
      (node (ref "LED213") (pin "A") (pinfunction "A_A") (pintype "passive"))
      (node (ref "LED214") (pin "A") (pinfunction "A_A") (pintype "passive"))
      (node (ref "LED215") (pin "A") (pinfunction "A_A") (pintype "passive"))
      (node (ref "LED216") (pin "A") (pinfunction "A_A") (pintype "passive"))
      (node (ref "LED217") (pin "A") (pinfunction "A_A") (pintype "passive"))
      (node (ref "LED218") (pin "A") (pinfunction "A_A") (pintype "passive"))
      (node (ref "LED219") (pin "A") (pinfunction "A_A") (pintype "passive"))
      (node (ref "LED220") (pin "A") (pinfunction "A_A") (pintype "passive"))
      (node (ref "LED221") (pin "A") (pinfunction "A_A") (pintype "passive"))
      (node (ref "LED222") (pin "A") (pinfunction "A_A") (pintype "passive"))
      (node (ref "LED223") (pin "A") (pinfunction "A_A") (pintype "passive"))
      (node (ref "LED224") (pin "A") (pinfunction "A_A") (pintype "passive"))
    )
    (net (code "5") (name "Net-(IC1A-QD)") (class "Default")
      (node (ref "IC1") (pin "3") (pinfunction "QD_3") (pintype "tri_state"))
      (node (ref "LED193") (pin "A") (pinfunction "A_A") (pintype "passive"))
      (node (ref "LED194") (pin "A") (pinfunction "A_A") (pintype "passive"))
      (node (ref "LED195") (pin "A") (pinfunction "A_A") (pintype "passive"))
      (node (ref "LED196") (pin "A") (pinfunction "A_A") (pintype "passive"))
      (node (ref "LED197") (pin "A") (pinfunction "A_A") (pintype "passive"))
      (node (ref "LED198") (pin "A") (pinfunction "A_A") (pintype "passive"))
      (node (ref "LED199") (pin "A") (pinfunction "A_A") (pintype "passive"))
      (node (ref "LED200") (pin "A") (pinfunction "A_A") (pintype "passive"))
      (node (ref "LED201") (pin "A") (pinfunction "A_A") (pintype "passive"))
      (node (ref "LED202") (pin "A") (pinfunction "A_A") (pintype "passive"))
      (node (ref "LED203") (pin "A") (pinfunction "A_A") (pintype "passive"))
      (node (ref "LED204") (pin "A") (pinfunction "A_A") (pintype "passive"))
      (node (ref "LED205") (pin "A") (pinfunction "A_A") (pintype "passive"))
      (node (ref "LED206") (pin "A") (pinfunction "A_A") (pintype "passive"))
      (node (ref "LED207") (pin "A") (pinfunction "A_A") (pintype "passive"))
      (node (ref "LED208") (pin "A") (pinfunction "A_A") (pintype "passive"))
    )
    (net (code "6") (name "Net-(IC1A-QE)") (class "Default")
      (node (ref "IC1") (pin "4") (pinfunction "QE_4") (pintype "tri_state"))
      (node (ref "LED177") (pin "A") (pinfunction "A_A") (pintype "passive"))
      (node (ref "LED178") (pin "A") (pinfunction "A_A") (pintype "passive"))
      (node (ref "LED179") (pin "A") (pinfunction "A_A") (pintype "passive"))
      (node (ref "LED180") (pin "A") (pinfunction "A_A") (pintype "passive"))
      (node (ref "LED181") (pin "A") (pinfunction "A_A") (pintype "passive"))
      (node (ref "LED182") (pin "A") (pinfunction "A_A") (pintype "passive"))
      (node (ref "LED183") (pin "A") (pinfunction "A_A") (pintype "passive"))
      (node (ref "LED184") (pin "A") (pinfunction "A_A") (pintype "passive"))
      (node (ref "LED185") (pin "A") (pinfunction "A_A") (pintype "passive"))
      (node (ref "LED186") (pin "A") (pinfunction "A_A") (pintype "passive"))
      (node (ref "LED187") (pin "A") (pinfunction "A_A") (pintype "passive"))
      (node (ref "LED188") (pin "A") (pinfunction "A_A") (pintype "passive"))
      (node (ref "LED189") (pin "A") (pinfunction "A_A") (pintype "passive"))
      (node (ref "LED190") (pin "A") (pinfunction "A_A") (pintype "passive"))
      (node (ref "LED191") (pin "A") (pinfunction "A_A") (pintype "passive"))
      (node (ref "LED192") (pin "A") (pinfunction "A_A") (pintype "passive"))
    )
    (net (code "7") (name "Net-(IC1A-QF)") (class "Default")
      (node (ref "IC1") (pin "5") (pinfunction "QF_5") (pintype "tri_state"))
      (node (ref "LED161") (pin "A") (pinfunction "A_A") (pintype "passive"))
      (node (ref "LED162") (pin "A") (pinfunction "A_A") (pintype "passive"))
      (node (ref "LED163") (pin "A") (pinfunction "A_A") (pintype "passive"))
      (node (ref "LED164") (pin "A") (pinfunction "A_A") (pintype "passive"))
      (node (ref "LED165") (pin "A") (pinfunction "A_A") (pintype "passive"))
      (node (ref "LED166") (pin "A") (pinfunction "A_A") (pintype "passive"))
      (node (ref "LED167") (pin "A") (pinfunction "A_A") (pintype "passive"))
      (node (ref "LED168") (pin "A") (pinfunction "A_A") (pintype "passive"))
      (node (ref "LED169") (pin "A") (pinfunction "A_A") (pintype "passive"))
      (node (ref "LED170") (pin "A") (pinfunction "A_A") (pintype "passive"))
      (node (ref "LED171") (pin "A") (pinfunction "A_A") (pintype "passive"))
      (node (ref "LED172") (pin "A") (pinfunction "A_A") (pintype "passive"))
      (node (ref "LED173") (pin "A") (pinfunction "A_A") (pintype "passive"))
      (node (ref "LED174") (pin "A") (pinfunction "A_A") (pintype "passive"))
      (node (ref "LED175") (pin "A") (pinfunction "A_A") (pintype "passive"))
      (node (ref "LED176") (pin "A") (pinfunction "A_A") (pintype "passive"))
    )
    (net (code "8") (name "Net-(IC1A-QG)") (class "Default")
      (node (ref "IC1") (pin "6") (pinfunction "QG_6") (pintype "tri_state"))
      (node (ref "LED145") (pin "A") (pinfunction "A_A") (pintype "passive"))
      (node (ref "LED146") (pin "A") (pinfunction "A_A") (pintype "passive"))
      (node (ref "LED147") (pin "A") (pinfunction "A_A") (pintype "passive"))
      (node (ref "LED148") (pin "A") (pinfunction "A_A") (pintype "passive"))
      (node (ref "LED149") (pin "A") (pinfunction "A_A") (pintype "passive"))
      (node (ref "LED150") (pin "A") (pinfunction "A_A") (pintype "passive"))
      (node (ref "LED151") (pin "A") (pinfunction "A_A") (pintype "passive"))
      (node (ref "LED152") (pin "A") (pinfunction "A_A") (pintype "passive"))
      (node (ref "LED153") (pin "A") (pinfunction "A_A") (pintype "passive"))
      (node (ref "LED154") (pin "A") (pinfunction "A_A") (pintype "passive"))
      (node (ref "LED155") (pin "A") (pinfunction "A_A") (pintype "passive"))
      (node (ref "LED156") (pin "A") (pinfunction "A_A") (pintype "passive"))
      (node (ref "LED157") (pin "A") (pinfunction "A_A") (pintype "passive"))
      (node (ref "LED158") (pin "A") (pinfunction "A_A") (pintype "passive"))
      (node (ref "LED159") (pin "A") (pinfunction "A_A") (pintype "passive"))
      (node (ref "LED160") (pin "A") (pinfunction "A_A") (pintype "passive"))
    )
    (net (code "9") (name "Net-(IC1A-QH)") (class "Default")
      (node (ref "IC1") (pin "7") (pinfunction "QH_7") (pintype "tri_state"))
      (node (ref "LED129") (pin "A") (pinfunction "A_A") (pintype "passive"))
      (node (ref "LED130") (pin "A") (pinfunction "A_A") (pintype "passive"))
      (node (ref "LED131") (pin "A") (pinfunction "A_A") (pintype "passive"))
      (node (ref "LED132") (pin "A") (pinfunction "A_A") (pintype "passive"))
      (node (ref "LED133") (pin "A") (pinfunction "A_A") (pintype "passive"))
      (node (ref "LED134") (pin "A") (pinfunction "A_A") (pintype "passive"))
      (node (ref "LED135") (pin "A") (pinfunction "A_A") (pintype "passive"))
      (node (ref "LED136") (pin "A") (pinfunction "A_A") (pintype "passive"))
      (node (ref "LED137") (pin "A") (pinfunction "A_A") (pintype "passive"))
      (node (ref "LED138") (pin "A") (pinfunction "A_A") (pintype "passive"))
      (node (ref "LED139") (pin "A") (pinfunction "A_A") (pintype "passive"))
      (node (ref "LED140") (pin "A") (pinfunction "A_A") (pintype "passive"))
      (node (ref "LED141") (pin "A") (pinfunction "A_A") (pintype "passive"))
      (node (ref "LED142") (pin "A") (pinfunction "A_A") (pintype "passive"))
      (node (ref "LED143") (pin "A") (pinfunction "A_A") (pintype "passive"))
      (node (ref "LED144") (pin "A") (pinfunction "A_A") (pintype "passive"))
    )
    (net (code "10") (name "Net-(IC1A-RCK)") (class "Default")
      (node (ref "IC1") (pin "12") (pinfunction "RCK_12") (pintype "input"))
      (node (ref "IC2") (pin "12") (pinfunction "RCK_12") (pintype "input"))
      (node (ref "J1") (pin "4") (pinfunction "4_4") (pintype "passive"))
    )
    (net (code "11") (name "Net-(IC1A-SCK)") (class "Default")
      (node (ref "IC1") (pin "11") (pinfunction "SCK_11") (pintype "input"))
      (node (ref "IC2") (pin "11") (pinfunction "SCK_11") (pintype "input"))
      (node (ref "J1") (pin "3") (pinfunction "3_3") (pintype "passive"))
    )
    (net (code "12") (name "Net-(IC1A-SER)") (class "Default")
      (node (ref "IC1") (pin "14") (pinfunction "SER_14") (pintype "input"))
      (node (ref "IC2") (pin "9") (pinfunction "QH*_9") (pintype "tri_state"))
    )
    (net (code "13") (name "Net-(IC2A-QA)") (class "Default")
      (node (ref "IC2") (pin "15") (pinfunction "QA_15") (pintype "tri_state"))
      (node (ref "LED113") (pin "A") (pinfunction "A_A") (pintype "passive"))
      (node (ref "LED114") (pin "A") (pinfunction "A_A") (pintype "passive"))
      (node (ref "LED115") (pin "A") (pinfunction "A_A") (pintype "passive"))
      (node (ref "LED116") (pin "A") (pinfunction "A_A") (pintype "passive"))
      (node (ref "LED117") (pin "A") (pinfunction "A_A") (pintype "passive"))
      (node (ref "LED118") (pin "A") (pinfunction "A_A") (pintype "passive"))
      (node (ref "LED119") (pin "A") (pinfunction "A_A") (pintype "passive"))
      (node (ref "LED120") (pin "A") (pinfunction "A_A") (pintype "passive"))
      (node (ref "LED121") (pin "A") (pinfunction "A_A") (pintype "passive"))
      (node (ref "LED122") (pin "A") (pinfunction "A_A") (pintype "passive"))
      (node (ref "LED123") (pin "A") (pinfunction "A_A") (pintype "passive"))
      (node (ref "LED124") (pin "A") (pinfunction "A_A") (pintype "passive"))
      (node (ref "LED125") (pin "A") (pinfunction "A_A") (pintype "passive"))
      (node (ref "LED126") (pin "A") (pinfunction "A_A") (pintype "passive"))
      (node (ref "LED127") (pin "A") (pinfunction "A_A") (pintype "passive"))
      (node (ref "LED128") (pin "A") (pinfunction "A_A") (pintype "passive"))
    )
    (net (code "14") (name "Net-(IC2A-QB)") (class "Default")
      (node (ref "IC2") (pin "1") (pinfunction "QB_1") (pintype "tri_state"))
      (node (ref "LED100") (pin "A") (pinfunction "A_A") (pintype "passive"))
      (node (ref "LED101") (pin "A") (pinfunction "A_A") (pintype "passive"))
      (node (ref "LED102") (pin "A") (pinfunction "A_A") (pintype "passive"))
      (node (ref "LED103") (pin "A") (pinfunction "A_A") (pintype "passive"))
      (node (ref "LED104") (pin "A") (pinfunction "A_A") (pintype "passive"))
      (node (ref "LED105") (pin "A") (pinfunction "A_A") (pintype "passive"))
      (node (ref "LED106") (pin "A") (pinfunction "A_A") (pintype "passive"))
      (node (ref "LED107") (pin "A") (pinfunction "A_A") (pintype "passive"))
      (node (ref "LED108") (pin "A") (pinfunction "A_A") (pintype "passive"))
      (node (ref "LED109") (pin "A") (pinfunction "A_A") (pintype "passive"))
      (node (ref "LED110") (pin "A") (pinfunction "A_A") (pintype "passive"))
      (node (ref "LED111") (pin "A") (pinfunction "A_A") (pintype "passive"))
      (node (ref "LED112") (pin "A") (pinfunction "A_A") (pintype "passive"))
      (node (ref "LED97") (pin "A") (pinfunction "A_A") (pintype "passive"))
      (node (ref "LED98") (pin "A") (pinfunction "A_A") (pintype "passive"))
      (node (ref "LED99") (pin "A") (pinfunction "A_A") (pintype "passive"))
    )
    (net (code "15") (name "Net-(IC2A-QC)") (class "Default")
      (node (ref "IC2") (pin "2") (pinfunction "QC_2") (pintype "tri_state"))
      (node (ref "LED81") (pin "A") (pinfunction "A_A") (pintype "passive"))
      (node (ref "LED82") (pin "A") (pinfunction "A_A") (pintype "passive"))
      (node (ref "LED83") (pin "A") (pinfunction "A_A") (pintype "passive"))
      (node (ref "LED84") (pin "A") (pinfunction "A_A") (pintype "passive"))
      (node (ref "LED85") (pin "A") (pinfunction "A_A") (pintype "passive"))
      (node (ref "LED86") (pin "A") (pinfunction "A_A") (pintype "passive"))
      (node (ref "LED87") (pin "A") (pinfunction "A_A") (pintype "passive"))
      (node (ref "LED88") (pin "A") (pinfunction "A_A") (pintype "passive"))
      (node (ref "LED89") (pin "A") (pinfunction "A_A") (pintype "passive"))
      (node (ref "LED90") (pin "A") (pinfunction "A_A") (pintype "passive"))
      (node (ref "LED91") (pin "A") (pinfunction "A_A") (pintype "passive"))
      (node (ref "LED92") (pin "A") (pinfunction "A_A") (pintype "passive"))
      (node (ref "LED93") (pin "A") (pinfunction "A_A") (pintype "passive"))
      (node (ref "LED94") (pin "A") (pinfunction "A_A") (pintype "passive"))
      (node (ref "LED95") (pin "A") (pinfunction "A_A") (pintype "passive"))
      (node (ref "LED96") (pin "A") (pinfunction "A_A") (pintype "passive"))
    )
    (net (code "16") (name "Net-(IC2A-QD)") (class "Default")
      (node (ref "IC2") (pin "3") (pinfunction "QD_3") (pintype "tri_state"))
      (node (ref "LED65") (pin "A") (pinfunction "A_A") (pintype "passive"))
      (node (ref "LED66") (pin "A") (pinfunction "A_A") (pintype "passive"))
      (node (ref "LED67") (pin "A") (pinfunction "A_A") (pintype "passive"))
      (node (ref "LED68") (pin "A") (pinfunction "A_A") (pintype "passive"))
      (node (ref "LED69") (pin "A") (pinfunction "A_A") (pintype "passive"))
      (node (ref "LED70") (pin "A") (pinfunction "A_A") (pintype "passive"))
      (node (ref "LED71") (pin "A") (pinfunction "A_A") (pintype "passive"))
      (node (ref "LED72") (pin "A") (pinfunction "A_A") (pintype "passive"))
      (node (ref "LED73") (pin "A") (pinfunction "A_A") (pintype "passive"))
      (node (ref "LED74") (pin "A") (pinfunction "A_A") (pintype "passive"))
      (node (ref "LED75") (pin "A") (pinfunction "A_A") (pintype "passive"))
      (node (ref "LED76") (pin "A") (pinfunction "A_A") (pintype "passive"))
      (node (ref "LED77") (pin "A") (pinfunction "A_A") (pintype "passive"))
      (node (ref "LED78") (pin "A") (pinfunction "A_A") (pintype "passive"))
      (node (ref "LED79") (pin "A") (pinfunction "A_A") (pintype "passive"))
      (node (ref "LED80") (pin "A") (pinfunction "A_A") (pintype "passive"))
    )
    (net (code "17") (name "Net-(IC2A-QE)") (class "Default")
      (node (ref "IC2") (pin "4") (pinfunction "QE_4") (pintype "tri_state"))
      (node (ref "LED49") (pin "A") (pinfunction "A_A") (pintype "passive"))
      (node (ref "LED50") (pin "A") (pinfunction "A_A") (pintype "passive"))
      (node (ref "LED51") (pin "A") (pinfunction "A_A") (pintype "passive"))
      (node (ref "LED52") (pin "A") (pinfunction "A_A") (pintype "passive"))
      (node (ref "LED53") (pin "A") (pinfunction "A_A") (pintype "passive"))
      (node (ref "LED54") (pin "A") (pinfunction "A_A") (pintype "passive"))
      (node (ref "LED55") (pin "A") (pinfunction "A_A") (pintype "passive"))
      (node (ref "LED56") (pin "A") (pinfunction "A_A") (pintype "passive"))
      (node (ref "LED57") (pin "A") (pinfunction "A_A") (pintype "passive"))
      (node (ref "LED58") (pin "A") (pinfunction "A_A") (pintype "passive"))
      (node (ref "LED59") (pin "A") (pinfunction "A_A") (pintype "passive"))
      (node (ref "LED60") (pin "A") (pinfunction "A_A") (pintype "passive"))
      (node (ref "LED61") (pin "A") (pinfunction "A_A") (pintype "passive"))
      (node (ref "LED62") (pin "A") (pinfunction "A_A") (pintype "passive"))
      (node (ref "LED63") (pin "A") (pinfunction "A_A") (pintype "passive"))
      (node (ref "LED64") (pin "A") (pinfunction "A_A") (pintype "passive"))
    )
    (net (code "18") (name "Net-(IC2A-QF)") (class "Default")
      (node (ref "IC2") (pin "5") (pinfunction "QF_5") (pintype "tri_state"))
      (node (ref "LED33") (pin "A") (pinfunction "A_A") (pintype "passive"))
      (node (ref "LED34") (pin "A") (pinfunction "A_A") (pintype "passive"))
      (node (ref "LED35") (pin "A") (pinfunction "A_A") (pintype "passive"))
      (node (ref "LED36") (pin "A") (pinfunction "A_A") (pintype "passive"))
      (node (ref "LED37") (pin "A") (pinfunction "A_A") (pintype "passive"))
      (node (ref "LED38") (pin "A") (pinfunction "A_A") (pintype "passive"))
      (node (ref "LED39") (pin "A") (pinfunction "A_A") (pintype "passive"))
      (node (ref "LED40") (pin "A") (pinfunction "A_A") (pintype "passive"))
      (node (ref "LED41") (pin "A") (pinfunction "A_A") (pintype "passive"))
      (node (ref "LED42") (pin "A") (pinfunction "A_A") (pintype "passive"))
      (node (ref "LED43") (pin "A") (pinfunction "A_A") (pintype "passive"))
      (node (ref "LED44") (pin "A") (pinfunction "A_A") (pintype "passive"))
      (node (ref "LED45") (pin "A") (pinfunction "A_A") (pintype "passive"))
      (node (ref "LED46") (pin "A") (pinfunction "A_A") (pintype "passive"))
      (node (ref "LED47") (pin "A") (pinfunction "A_A") (pintype "passive"))
      (node (ref "LED48") (pin "A") (pinfunction "A_A") (pintype "passive"))
    )
    (net (code "19") (name "Net-(IC2A-QG)") (class "Default")
      (node (ref "IC2") (pin "6") (pinfunction "QG_6") (pintype "tri_state"))
      (node (ref "LED17") (pin "A") (pinfunction "A_A") (pintype "passive"))
      (node (ref "LED18") (pin "A") (pinfunction "A_A") (pintype "passive"))
      (node (ref "LED19") (pin "A") (pinfunction "A_A") (pintype "passive"))
      (node (ref "LED20") (pin "A") (pinfunction "A_A") (pintype "passive"))
      (node (ref "LED21") (pin "A") (pinfunction "A_A") (pintype "passive"))
      (node (ref "LED22") (pin "A") (pinfunction "A_A") (pintype "passive"))
      (node (ref "LED23") (pin "A") (pinfunction "A_A") (pintype "passive"))
      (node (ref "LED24") (pin "A") (pinfunction "A_A") (pintype "passive"))
      (node (ref "LED25") (pin "A") (pinfunction "A_A") (pintype "passive"))
      (node (ref "LED26") (pin "A") (pinfunction "A_A") (pintype "passive"))
      (node (ref "LED27") (pin "A") (pinfunction "A_A") (pintype "passive"))
      (node (ref "LED28") (pin "A") (pinfunction "A_A") (pintype "passive"))
      (node (ref "LED29") (pin "A") (pinfunction "A_A") (pintype "passive"))
      (node (ref "LED30") (pin "A") (pinfunction "A_A") (pintype "passive"))
      (node (ref "LED31") (pin "A") (pinfunction "A_A") (pintype "passive"))
      (node (ref "LED32") (pin "A") (pinfunction "A_A") (pintype "passive"))
    )
    (net (code "20") (name "Net-(IC2A-QH)") (class "Default")
      (node (ref "IC2") (pin "7") (pinfunction "QH_7") (pintype "tri_state"))
      (node (ref "LED1") (pin "A") (pinfunction "A_A") (pintype "passive"))
      (node (ref "LED10") (pin "A") (pinfunction "A_A") (pintype "passive"))
      (node (ref "LED11") (pin "A") (pinfunction "A_A") (pintype "passive"))
      (node (ref "LED12") (pin "A") (pinfunction "A_A") (pintype "passive"))
      (node (ref "LED13") (pin "A") (pinfunction "A_A") (pintype "passive"))
      (node (ref "LED14") (pin "A") (pinfunction "A_A") (pintype "passive"))
      (node (ref "LED15") (pin "A") (pinfunction "A_A") (pintype "passive"))
      (node (ref "LED16") (pin "A") (pinfunction "A_A") (pintype "passive"))
      (node (ref "LED2") (pin "A") (pinfunction "A_A") (pintype "passive"))
      (node (ref "LED3") (pin "A") (pinfunction "A_A") (pintype "passive"))
      (node (ref "LED4") (pin "A") (pinfunction "A_A") (pintype "passive"))
      (node (ref "LED5") (pin "A") (pinfunction "A_A") (pintype "passive"))
      (node (ref "LED6") (pin "A") (pinfunction "A_A") (pintype "passive"))
      (node (ref "LED7") (pin "A") (pinfunction "A_A") (pintype "passive"))
      (node (ref "LED8") (pin "A") (pinfunction "A_A") (pintype "passive"))
      (node (ref "LED9") (pin "A") (pinfunction "A_A") (pintype "passive"))
    )
    (net (code "21") (name "Net-(IC2A-SER)") (class "Default")
      (node (ref "IC2") (pin "14") (pinfunction "SER_14") (pintype "input"))
      (node (ref "J1") (pin "5") (pinfunction "5_5") (pintype "passive"))
    )
    (net (code "22") (name "Net-(IC3A-G)") (class "Default")
      (node (ref "IC3") (pin "13") (pinfunction "G_13") (pintype "input"))
      (node (ref "IC4") (pin "13") (pinfunction "G_13") (pintype "input"))
    )
    (net (code "23") (name "Net-(IC3A-QA)") (class "Default")
      (node (ref "IC3") (pin "15") (pinfunction "QA_15") (pintype "tri_state"))
      (node (ref "LED104") (pin "K") (pinfunction "C_K") (pintype "passive"))
      (node (ref "LED120") (pin "K") (pinfunction "C_K") (pintype "passive"))
      (node (ref "LED136") (pin "K") (pinfunction "C_K") (pintype "passive"))
      (node (ref "LED152") (pin "K") (pinfunction "C_K") (pintype "passive"))
      (node (ref "LED168") (pin "K") (pinfunction "C_K") (pintype "passive"))
      (node (ref "LED184") (pin "K") (pinfunction "C_K") (pintype "passive"))
      (node (ref "LED200") (pin "K") (pinfunction "C_K") (pintype "passive"))
      (node (ref "LED216") (pin "K") (pinfunction "C_K") (pintype "passive"))
      (node (ref "LED232") (pin "K") (pinfunction "C_K") (pintype "passive"))
      (node (ref "LED24") (pin "K") (pinfunction "C_K") (pintype "passive"))
      (node (ref "LED248") (pin "K") (pinfunction "C_K") (pintype "passive"))
      (node (ref "LED40") (pin "K") (pinfunction "C_K") (pintype "passive"))
      (node (ref "LED56") (pin "K") (pinfunction "C_K") (pintype "passive"))
      (node (ref "LED72") (pin "K") (pinfunction "C_K") (pintype "passive"))
      (node (ref "LED8") (pin "K") (pinfunction "C_K") (pintype "passive"))
      (node (ref "LED88") (pin "K") (pinfunction "C_K") (pintype "passive"))
    )
    (net (code "24") (name "Net-(IC3A-QB)") (class "Default")
      (node (ref "IC3") (pin "1") (pinfunction "QB_1") (pintype "tri_state"))
      (node (ref "LED103") (pin "K") (pinfunction "C_K") (pintype "passive"))
      (node (ref "LED119") (pin "K") (pinfunction "C_K") (pintype "passive"))
      (node (ref "LED135") (pin "K") (pinfunction "C_K") (pintype "passive"))
      (node (ref "LED151") (pin "K") (pinfunction "C_K") (pintype "passive"))
      (node (ref "LED167") (pin "K") (pinfunction "C_K") (pintype "passive"))
      (node (ref "LED183") (pin "K") (pinfunction "C_K") (pintype "passive"))
      (node (ref "LED199") (pin "K") (pinfunction "C_K") (pintype "passive"))
      (node (ref "LED215") (pin "K") (pinfunction "C_K") (pintype "passive"))
      (node (ref "LED23") (pin "K") (pinfunction "C_K") (pintype "passive"))
      (node (ref "LED231") (pin "K") (pinfunction "C_K") (pintype "passive"))
      (node (ref "LED247") (pin "K") (pinfunction "C_K") (pintype "passive"))
      (node (ref "LED39") (pin "K") (pinfunction "C_K") (pintype "passive"))
      (node (ref "LED55") (pin "K") (pinfunction "C_K") (pintype "passive"))
      (node (ref "LED7") (pin "K") (pinfunction "C_K") (pintype "passive"))
      (node (ref "LED71") (pin "K") (pinfunction "C_K") (pintype "passive"))
      (node (ref "LED87") (pin "K") (pinfunction "C_K") (pintype "passive"))
    )
    (net (code "25") (name "Net-(IC3A-QC)") (class "Default")
      (node (ref "IC3") (pin "2") (pinfunction "QC_2") (pintype "tri_state"))
      (node (ref "LED102") (pin "K") (pinfunction "C_K") (pintype "passive"))
      (node (ref "LED118") (pin "K") (pinfunction "C_K") (pintype "passive"))
      (node (ref "LED134") (pin "K") (pinfunction "C_K") (pintype "passive"))
      (node (ref "LED150") (pin "K") (pinfunction "C_K") (pintype "passive"))
      (node (ref "LED166") (pin "K") (pinfunction "C_K") (pintype "passive"))
      (node (ref "LED182") (pin "K") (pinfunction "C_K") (pintype "passive"))
      (node (ref "LED198") (pin "K") (pinfunction "C_K") (pintype "passive"))
      (node (ref "LED214") (pin "K") (pinfunction "C_K") (pintype "passive"))
      (node (ref "LED22") (pin "K") (pinfunction "C_K") (pintype "passive"))
      (node (ref "LED230") (pin "K") (pinfunction "C_K") (pintype "passive"))
      (node (ref "LED246") (pin "K") (pinfunction "C_K") (pintype "passive"))
      (node (ref "LED38") (pin "K") (pinfunction "C_K") (pintype "passive"))
      (node (ref "LED54") (pin "K") (pinfunction "C_K") (pintype "passive"))
      (node (ref "LED6") (pin "K") (pinfunction "C_K") (pintype "passive"))
      (node (ref "LED70") (pin "K") (pinfunction "C_K") (pintype "passive"))
      (node (ref "LED86") (pin "K") (pinfunction "C_K") (pintype "passive"))
    )
    (net (code "26") (name "Net-(IC3A-QD)") (class "Default")
      (node (ref "IC3") (pin "3") (pinfunction "QD_3") (pintype "tri_state"))
      (node (ref "LED101") (pin "K") (pinfunction "C_K") (pintype "passive"))
      (node (ref "LED117") (pin "K") (pinfunction "C_K") (pintype "passive"))
      (node (ref "LED133") (pin "K") (pinfunction "C_K") (pintype "passive"))
      (node (ref "LED149") (pin "K") (pinfunction "C_K") (pintype "passive"))
      (node (ref "LED165") (pin "K") (pinfunction "C_K") (pintype "passive"))
      (node (ref "LED181") (pin "K") (pinfunction "C_K") (pintype "passive"))
      (node (ref "LED197") (pin "K") (pinfunction "C_K") (pintype "passive"))
      (node (ref "LED21") (pin "K") (pinfunction "C_K") (pintype "passive"))
      (node (ref "LED213") (pin "K") (pinfunction "C_K") (pintype "passive"))
      (node (ref "LED229") (pin "K") (pinfunction "C_K") (pintype "passive"))
      (node (ref "LED245") (pin "K") (pinfunction "C_K") (pintype "passive"))
      (node (ref "LED37") (pin "K") (pinfunction "C_K") (pintype "passive"))
      (node (ref "LED5") (pin "K") (pinfunction "C_K") (pintype "passive"))
      (node (ref "LED53") (pin "K") (pinfunction "C_K") (pintype "passive"))
      (node (ref "LED69") (pin "K") (pinfunction "C_K") (pintype "passive"))
      (node (ref "LED85") (pin "K") (pinfunction "C_K") (pintype "passive"))
    )
    (net (code "27") (name "Net-(IC3A-QE)") (class "Default")
      (node (ref "IC3") (pin "4") (pinfunction "QE_4") (pintype "tri_state"))
      (node (ref "LED100") (pin "K") (pinfunction "C_K") (pintype "passive"))
      (node (ref "LED116") (pin "K") (pinfunction "C_K") (pintype "passive"))
      (node (ref "LED132") (pin "K") (pinfunction "C_K") (pintype "passive"))
      (node (ref "LED148") (pin "K") (pinfunction "C_K") (pintype "passive"))
      (node (ref "LED164") (pin "K") (pinfunction "C_K") (pintype "passive"))
      (node (ref "LED180") (pin "K") (pinfunction "C_K") (pintype "passive"))
      (node (ref "LED196") (pin "K") (pinfunction "C_K") (pintype "passive"))
      (node (ref "LED20") (pin "K") (pinfunction "C_K") (pintype "passive"))
      (node (ref "LED212") (pin "K") (pinfunction "C_K") (pintype "passive"))
      (node (ref "LED228") (pin "K") (pinfunction "C_K") (pintype "passive"))
      (node (ref "LED244") (pin "K") (pinfunction "C_K") (pintype "passive"))
      (node (ref "LED36") (pin "K") (pinfunction "C_K") (pintype "passive"))
      (node (ref "LED4") (pin "K") (pinfunction "C_K") (pintype "passive"))
      (node (ref "LED52") (pin "K") (pinfunction "C_K") (pintype "passive"))
      (node (ref "LED68") (pin "K") (pinfunction "C_K") (pintype "passive"))
      (node (ref "LED84") (pin "K") (pinfunction "C_K") (pintype "passive"))
    )
    (net (code "28") (name "Net-(IC3A-QF)") (class "Default")
      (node (ref "IC3") (pin "5") (pinfunction "QF_5") (pintype "tri_state"))
      (node (ref "LED115") (pin "K") (pinfunction "C_K") (pintype "passive"))
      (node (ref "LED131") (pin "K") (pinfunction "C_K") (pintype "passive"))
      (node (ref "LED147") (pin "K") (pinfunction "C_K") (pintype "passive"))
      (node (ref "LED163") (pin "K") (pinfunction "C_K") (pintype "passive"))
      (node (ref "LED179") (pin "K") (pinfunction "C_K") (pintype "passive"))
      (node (ref "LED19") (pin "K") (pinfunction "C_K") (pintype "passive"))
      (node (ref "LED195") (pin "K") (pinfunction "C_K") (pintype "passive"))
      (node (ref "LED211") (pin "K") (pinfunction "C_K") (pintype "passive"))
      (node (ref "LED227") (pin "K") (pinfunction "C_K") (pintype "passive"))
      (node (ref "LED243") (pin "K") (pinfunction "C_K") (pintype "passive"))
      (node (ref "LED3") (pin "K") (pinfunction "C_K") (pintype "passive"))
      (node (ref "LED35") (pin "K") (pinfunction "C_K") (pintype "passive"))
      (node (ref "LED51") (pin "K") (pinfunction "C_K") (pintype "passive"))
      (node (ref "LED67") (pin "K") (pinfunction "C_K") (pintype "passive"))
      (node (ref "LED83") (pin "K") (pinfunction "C_K") (pintype "passive"))
      (node (ref "LED99") (pin "K") (pinfunction "C_K") (pintype "passive"))
    )
    (net (code "29") (name "Net-(IC3A-QG)") (class "Default")
      (node (ref "IC3") (pin "6") (pinfunction "QG_6") (pintype "tri_state"))
      (node (ref "LED114") (pin "K") (pinfunction "C_K") (pintype "passive"))
      (node (ref "LED130") (pin "K") (pinfunction "C_K") (pintype "passive"))
      (node (ref "LED146") (pin "K") (pinfunction "C_K") (pintype "passive"))
      (node (ref "LED162") (pin "K") (pinfunction "C_K") (pintype "passive"))
      (node (ref "LED178") (pin "K") (pinfunction "C_K") (pintype "passive"))
      (node (ref "LED18") (pin "K") (pinfunction "C_K") (pintype "passive"))
      (node (ref "LED194") (pin "K") (pinfunction "C_K") (pintype "passive"))
      (node (ref "LED2") (pin "K") (pinfunction "C_K") (pintype "passive"))
      (node (ref "LED210") (pin "K") (pinfunction "C_K") (pintype "passive"))
      (node (ref "LED226") (pin "K") (pinfunction "C_K") (pintype "passive"))
      (node (ref "LED242") (pin "K") (pinfunction "C_K") (pintype "passive"))
      (node (ref "LED34") (pin "K") (pinfunction "C_K") (pintype "passive"))
      (node (ref "LED50") (pin "K") (pinfunction "C_K") (pintype "passive"))
      (node (ref "LED66") (pin "K") (pinfunction "C_K") (pintype "passive"))
      (node (ref "LED82") (pin "K") (pinfunction "C_K") (pintype "passive"))
      (node (ref "LED98") (pin "K") (pinfunction "C_K") (pintype "passive"))
    )
    (net (code "30") (name "Net-(IC3A-QH)") (class "Default")
      (node (ref "IC3") (pin "7") (pinfunction "QH_7") (pintype "tri_state"))
      (node (ref "LED1") (pin "K") (pinfunction "C_K") (pintype "passive"))
      (node (ref "LED113") (pin "K") (pinfunction "C_K") (pintype "passive"))
      (node (ref "LED129") (pin "K") (pinfunction "C_K") (pintype "passive"))
      (node (ref "LED145") (pin "K") (pinfunction "C_K") (pintype "passive"))
      (node (ref "LED161") (pin "K") (pinfunction "C_K") (pintype "passive"))
      (node (ref "LED17") (pin "K") (pinfunction "C_K") (pintype "passive"))
      (node (ref "LED177") (pin "K") (pinfunction "C_K") (pintype "passive"))
      (node (ref "LED193") (pin "K") (pinfunction "C_K") (pintype "passive"))
      (node (ref "LED209") (pin "K") (pinfunction "C_K") (pintype "passive"))
      (node (ref "LED225") (pin "K") (pinfunction "C_K") (pintype "passive"))
      (node (ref "LED241") (pin "K") (pinfunction "C_K") (pintype "passive"))
      (node (ref "LED33") (pin "K") (pinfunction "C_K") (pintype "passive"))
      (node (ref "LED49") (pin "K") (pinfunction "C_K") (pintype "passive"))
      (node (ref "LED65") (pin "K") (pinfunction "C_K") (pintype "passive"))
      (node (ref "LED81") (pin "K") (pinfunction "C_K") (pintype "passive"))
      (node (ref "LED97") (pin "K") (pinfunction "C_K") (pintype "passive"))
    )
    (net (code "31") (name "Net-(IC3A-QH*)") (class "Default")
      (node (ref "IC3") (pin "9") (pinfunction "QH*_9") (pintype "tri_state"))
      (node (ref "IC4") (pin "14") (pinfunction "SER_14") (pintype "input"))
    )
    (net (code "32") (name "Net-(IC3A-RCK)") (class "Default")
      (node (ref "IC3") (pin "12") (pinfunction "RCK_12") (pintype "input"))
      (node (ref "IC4") (pin "12") (pinfunction "RCK_12") (pintype "input"))
      (node (ref "J1") (pin "9") (pinfunction "9_9") (pintype "passive"))
    )
    (net (code "33") (name "Net-(IC3A-SCK)") (class "Default")
      (node (ref "IC3") (pin "11") (pinfunction "SCK_11") (pintype "input"))
      (node (ref "IC4") (pin "11") (pinfunction "SCK_11") (pintype "input"))
      (node (ref "J1") (pin "8") (pinfunction "8_8") (pintype "passive"))
    )
    (net (code "34") (name "Net-(IC3A-SER)") (class "Default")
      (node (ref "IC3") (pin "14") (pinfunction "SER_14") (pintype "input"))
      (node (ref "J1") (pin "10") (pinfunction "10_10") (pintype "passive"))
    )
    (net (code "35") (name "Net-(IC4A-QA)") (class "Default")
      (node (ref "IC4") (pin "15") (pinfunction "QA_15") (pintype "tri_state"))
      (node (ref "LED112") (pin "K") (pinfunction "C_K") (pintype "passive"))
      (node (ref "LED128") (pin "K") (pinfunction "C_K") (pintype "passive"))
      (node (ref "LED144") (pin "K") (pinfunction "C_K") (pintype "passive"))
      (node (ref "LED16") (pin "K") (pinfunction "C_K") (pintype "passive"))
      (node (ref "LED160") (pin "K") (pinfunction "C_K") (pintype "passive"))
      (node (ref "LED176") (pin "K") (pinfunction "C_K") (pintype "passive"))
      (node (ref "LED192") (pin "K") (pinfunction "C_K") (pintype "passive"))
      (node (ref "LED208") (pin "K") (pinfunction "C_K") (pintype "passive"))
      (node (ref "LED224") (pin "K") (pinfunction "C_K") (pintype "passive"))
      (node (ref "LED240") (pin "K") (pinfunction "C_K") (pintype "passive"))
      (node (ref "LED256") (pin "K") (pinfunction "C_K") (pintype "passive"))
      (node (ref "LED32") (pin "K") (pinfunction "C_K") (pintype "passive"))
      (node (ref "LED48") (pin "K") (pinfunction "C_K") (pintype "passive"))
      (node (ref "LED64") (pin "K") (pinfunction "C_K") (pintype "passive"))
      (node (ref "LED80") (pin "K") (pinfunction "C_K") (pintype "passive"))
      (node (ref "LED96") (pin "K") (pinfunction "C_K") (pintype "passive"))
    )
    (net (code "36") (name "Net-(IC4A-QB)") (class "Default")
      (node (ref "IC4") (pin "1") (pinfunction "QB_1") (pintype "tri_state"))
      (node (ref "LED111") (pin "K") (pinfunction "C_K") (pintype "passive"))
      (node (ref "LED127") (pin "K") (pinfunction "C_K") (pintype "passive"))
      (node (ref "LED143") (pin "K") (pinfunction "C_K") (pintype "passive"))
      (node (ref "LED15") (pin "K") (pinfunction "C_K") (pintype "passive"))
      (node (ref "LED159") (pin "K") (pinfunction "C_K") (pintype "passive"))
      (node (ref "LED175") (pin "K") (pinfunction "C_K") (pintype "passive"))
      (node (ref "LED191") (pin "K") (pinfunction "C_K") (pintype "passive"))
      (node (ref "LED207") (pin "K") (pinfunction "C_K") (pintype "passive"))
      (node (ref "LED223") (pin "K") (pinfunction "C_K") (pintype "passive"))
      (node (ref "LED239") (pin "K") (pinfunction "C_K") (pintype "passive"))
      (node (ref "LED255") (pin "K") (pinfunction "C_K") (pintype "passive"))
      (node (ref "LED31") (pin "K") (pinfunction "C_K") (pintype "passive"))
      (node (ref "LED47") (pin "K") (pinfunction "C_K") (pintype "passive"))
      (node (ref "LED63") (pin "K") (pinfunction "C_K") (pintype "passive"))
      (node (ref "LED79") (pin "K") (pinfunction "C_K") (pintype "passive"))
      (node (ref "LED95") (pin "K") (pinfunction "C_K") (pintype "passive"))
    )
    (net (code "37") (name "Net-(IC4A-QC)") (class "Default")
      (node (ref "IC4") (pin "2") (pinfunction "QC_2") (pintype "tri_state"))
      (node (ref "LED110") (pin "K") (pinfunction "C_K") (pintype "passive"))
      (node (ref "LED126") (pin "K") (pinfunction "C_K") (pintype "passive"))
      (node (ref "LED14") (pin "K") (pinfunction "C_K") (pintype "passive"))
      (node (ref "LED142") (pin "K") (pinfunction "C_K") (pintype "passive"))
      (node (ref "LED158") (pin "K") (pinfunction "C_K") (pintype "passive"))
      (node (ref "LED174") (pin "K") (pinfunction "C_K") (pintype "passive"))
      (node (ref "LED190") (pin "K") (pinfunction "C_K") (pintype "passive"))
      (node (ref "LED206") (pin "K") (pinfunction "C_K") (pintype "passive"))
      (node (ref "LED222") (pin "K") (pinfunction "C_K") (pintype "passive"))
      (node (ref "LED238") (pin "K") (pinfunction "C_K") (pintype "passive"))
      (node (ref "LED254") (pin "K") (pinfunction "C_K") (pintype "passive"))
      (node (ref "LED30") (pin "K") (pinfunction "C_K") (pintype "passive"))
      (node (ref "LED46") (pin "K") (pinfunction "C_K") (pintype "passive"))
      (node (ref "LED62") (pin "K") (pinfunction "C_K") (pintype "passive"))
      (node (ref "LED78") (pin "K") (pinfunction "C_K") (pintype "passive"))
      (node (ref "LED94") (pin "K") (pinfunction "C_K") (pintype "passive"))
    )
    (net (code "38") (name "Net-(IC4A-QD)") (class "Default")
      (node (ref "IC4") (pin "3") (pinfunction "QD_3") (pintype "tri_state"))
      (node (ref "LED109") (pin "K") (pinfunction "C_K") (pintype "passive"))
      (node (ref "LED125") (pin "K") (pinfunction "C_K") (pintype "passive"))
      (node (ref "LED13") (pin "K") (pinfunction "C_K") (pintype "passive"))
      (node (ref "LED141") (pin "K") (pinfunction "C_K") (pintype "passive"))
      (node (ref "LED157") (pin "K") (pinfunction "C_K") (pintype "passive"))
      (node (ref "LED173") (pin "K") (pinfunction "C_K") (pintype "passive"))
      (node (ref "LED189") (pin "K") (pinfunction "C_K") (pintype "passive"))
      (node (ref "LED205") (pin "K") (pinfunction "C_K") (pintype "passive"))
      (node (ref "LED221") (pin "K") (pinfunction "C_K") (pintype "passive"))
      (node (ref "LED237") (pin "K") (pinfunction "C_K") (pintype "passive"))
      (node (ref "LED253") (pin "K") (pinfunction "C_K") (pintype "passive"))
      (node (ref "LED29") (pin "K") (pinfunction "C_K") (pintype "passive"))
      (node (ref "LED45") (pin "K") (pinfunction "C_K") (pintype "passive"))
      (node (ref "LED61") (pin "K") (pinfunction "C_K") (pintype "passive"))
      (node (ref "LED77") (pin "K") (pinfunction "C_K") (pintype "passive"))
      (node (ref "LED93") (pin "K") (pinfunction "C_K") (pintype "passive"))
    )
    (net (code "39") (name "Net-(IC4A-QE)") (class "Default")
      (node (ref "IC4") (pin "4") (pinfunction "QE_4") (pintype "tri_state"))
      (node (ref "LED108") (pin "K") (pinfunction "C_K") (pintype "passive"))
      (node (ref "LED12") (pin "K") (pinfunction "C_K") (pintype "passive"))
      (node (ref "LED124") (pin "K") (pinfunction "C_K") (pintype "passive"))
      (node (ref "LED140") (pin "K") (pinfunction "C_K") (pintype "passive"))
      (node (ref "LED156") (pin "K") (pinfunction "C_K") (pintype "passive"))
      (node (ref "LED172") (pin "K") (pinfunction "C_K") (pintype "passive"))
      (node (ref "LED188") (pin "K") (pinfunction "C_K") (pintype "passive"))
      (node (ref "LED204") (pin "K") (pinfunction "C_K") (pintype "passive"))
      (node (ref "LED220") (pin "K") (pinfunction "C_K") (pintype "passive"))
      (node (ref "LED236") (pin "K") (pinfunction "C_K") (pintype "passive"))
      (node (ref "LED252") (pin "K") (pinfunction "C_K") (pintype "passive"))
      (node (ref "LED28") (pin "K") (pinfunction "C_K") (pintype "passive"))
      (node (ref "LED44") (pin "K") (pinfunction "C_K") (pintype "passive"))
      (node (ref "LED60") (pin "K") (pinfunction "C_K") (pintype "passive"))
      (node (ref "LED76") (pin "K") (pinfunction "C_K") (pintype "passive"))
      (node (ref "LED92") (pin "K") (pinfunction "C_K") (pintype "passive"))
    )
    (net (code "40") (name "Net-(IC4A-QF)") (class "Default")
      (node (ref "IC4") (pin "5") (pinfunction "QF_5") (pintype "tri_state"))
      (node (ref "LED107") (pin "K") (pinfunction "C_K") (pintype "passive"))
      (node (ref "LED11") (pin "K") (pinfunction "C_K") (pintype "passive"))
      (node (ref "LED123") (pin "K") (pinfunction "C_K") (pintype "passive"))
      (node (ref "LED139") (pin "K") (pinfunction "C_K") (pintype "passive"))
      (node (ref "LED155") (pin "K") (pinfunction "C_K") (pintype "passive"))
      (node (ref "LED171") (pin "K") (pinfunction "C_K") (pintype "passive"))
      (node (ref "LED187") (pin "K") (pinfunction "C_K") (pintype "passive"))
      (node (ref "LED203") (pin "K") (pinfunction "C_K") (pintype "passive"))
      (node (ref "LED219") (pin "K") (pinfunction "C_K") (pintype "passive"))
      (node (ref "LED235") (pin "K") (pinfunction "C_K") (pintype "passive"))
      (node (ref "LED251") (pin "K") (pinfunction "C_K") (pintype "passive"))
      (node (ref "LED27") (pin "K") (pinfunction "C_K") (pintype "passive"))
      (node (ref "LED43") (pin "K") (pinfunction "C_K") (pintype "passive"))
      (node (ref "LED59") (pin "K") (pinfunction "C_K") (pintype "passive"))
      (node (ref "LED75") (pin "K") (pinfunction "C_K") (pintype "passive"))
      (node (ref "LED91") (pin "K") (pinfunction "C_K") (pintype "passive"))
    )
    (net (code "41") (name "Net-(IC4A-QG)") (class "Default")
      (node (ref "IC4") (pin "6") (pinfunction "QG_6") (pintype "tri_state"))
      (node (ref "LED10") (pin "K") (pinfunction "C_K") (pintype "passive"))
      (node (ref "LED106") (pin "K") (pinfunction "C_K") (pintype "passive"))
      (node (ref "LED122") (pin "K") (pinfunction "C_K") (pintype "passive"))
      (node (ref "LED138") (pin "K") (pinfunction "C_K") (pintype "passive"))
      (node (ref "LED154") (pin "K") (pinfunction "C_K") (pintype "passive"))
      (node (ref "LED170") (pin "K") (pinfunction "C_K") (pintype "passive"))
      (node (ref "LED186") (pin "K") (pinfunction "C_K") (pintype "passive"))
      (node (ref "LED202") (pin "K") (pinfunction "C_K") (pintype "passive"))
      (node (ref "LED218") (pin "K") (pinfunction "C_K") (pintype "passive"))
      (node (ref "LED234") (pin "K") (pinfunction "C_K") (pintype "passive"))
      (node (ref "LED250") (pin "K") (pinfunction "C_K") (pintype "passive"))
      (node (ref "LED26") (pin "K") (pinfunction "C_K") (pintype "passive"))
      (node (ref "LED42") (pin "K") (pinfunction "C_K") (pintype "passive"))
      (node (ref "LED58") (pin "K") (pinfunction "C_K") (pintype "passive"))
      (node (ref "LED74") (pin "K") (pinfunction "C_K") (pintype "passive"))
      (node (ref "LED90") (pin "K") (pinfunction "C_K") (pintype "passive"))
    )
    (net (code "42") (name "Net-(IC4A-QH)") (class "Default")
      (node (ref "IC4") (pin "7") (pinfunction "QH_7") (pintype "tri_state"))
      (node (ref "LED105") (pin "K") (pinfunction "C_K") (pintype "passive"))
      (node (ref "LED121") (pin "K") (pinfunction "C_K") (pintype "passive"))
      (node (ref "LED137") (pin "K") (pinfunction "C_K") (pintype "passive"))
      (node (ref "LED153") (pin "K") (pinfunction "C_K") (pintype "passive"))
      (node (ref "LED169") (pin "K") (pinfunction "C_K") (pintype "passive"))
      (node (ref "LED185") (pin "K") (pinfunction "C_K") (pintype "passive"))
      (node (ref "LED201") (pin "K") (pinfunction "C_K") (pintype "passive"))
      (node (ref "LED217") (pin "K") (pinfunction "C_K") (pintype "passive"))
      (node (ref "LED233") (pin "K") (pinfunction "C_K") (pintype "passive"))
      (node (ref "LED249") (pin "K") (pinfunction "C_K") (pintype "passive"))
      (node (ref "LED25") (pin "K") (pinfunction "C_K") (pintype "passive"))
      (node (ref "LED41") (pin "K") (pinfunction "C_K") (pintype "passive"))
      (node (ref "LED57") (pin "K") (pinfunction "C_K") (pintype "passive"))
      (node (ref "LED73") (pin "K") (pinfunction "C_K") (pintype "passive"))
      (node (ref "LED89") (pin "K") (pinfunction "C_K") (pintype "passive"))
      (node (ref "LED9") (pin "K") (pinfunction "C_K") (pintype "passive"))
    )
    (net (code "43") (name "VCC") (class "Default")
      (node (ref "IC1") (pin "10") (pinfunction "SCL_10") (pintype "input"))
      (node (ref "IC2") (pin "10") (pinfunction "SCL_10") (pintype "input"))
      (node (ref "IC3") (pin "10") (pinfunction "SCL_10") (pintype "input"))
      (node (ref "IC4") (pin "10") (pinfunction "SCL_10") (pintype "input"))
      (node (ref "J1") (pin "1") (pinfunction "1_1") (pintype "passive"))
    )
    (net (code "44") (name "unconnected-(IC1A-QH*-Pad9)") (class "Default")
      (node (ref "IC1") (pin "9") (pinfunction "QH*_9") (pintype "tri_state"))
    )
    (net (code "45") (name "unconnected-(IC4A-QH*-Pad9)") (class "Default")
      (node (ref "IC4") (pin "9") (pinfunction "QH*_9") (pintype "tri_state"))
    )
    (net (code "46") (name "unconnected-(J1-Pad2)") (class "Default")
      (node (ref "J1") (pin "2") (pinfunction "2_2") (pintype "passive"))
    )
    (net (code "47") (name "unconnected-(J1-Pad6)") (class "Default")
      (node (ref "J1") (pin "6") (pinfunction "6_6") (pintype "passive"))
    )
    (net (code "48") (name "unconnected-(J1-Pad7)") (class "Default")
      (node (ref "J1") (pin "7") (pinfunction "7_7") (pintype "passive"))
    )
    (net (code "49") (name "unconnected-(J1-Pad11)") (class "Default")
      (node (ref "J1") (pin "11") (pinfunction "11_11") (pintype "passive"))
    )
  )
)
